# EL00117.net
KiCad netlist of a schematic drawn in EAGLE
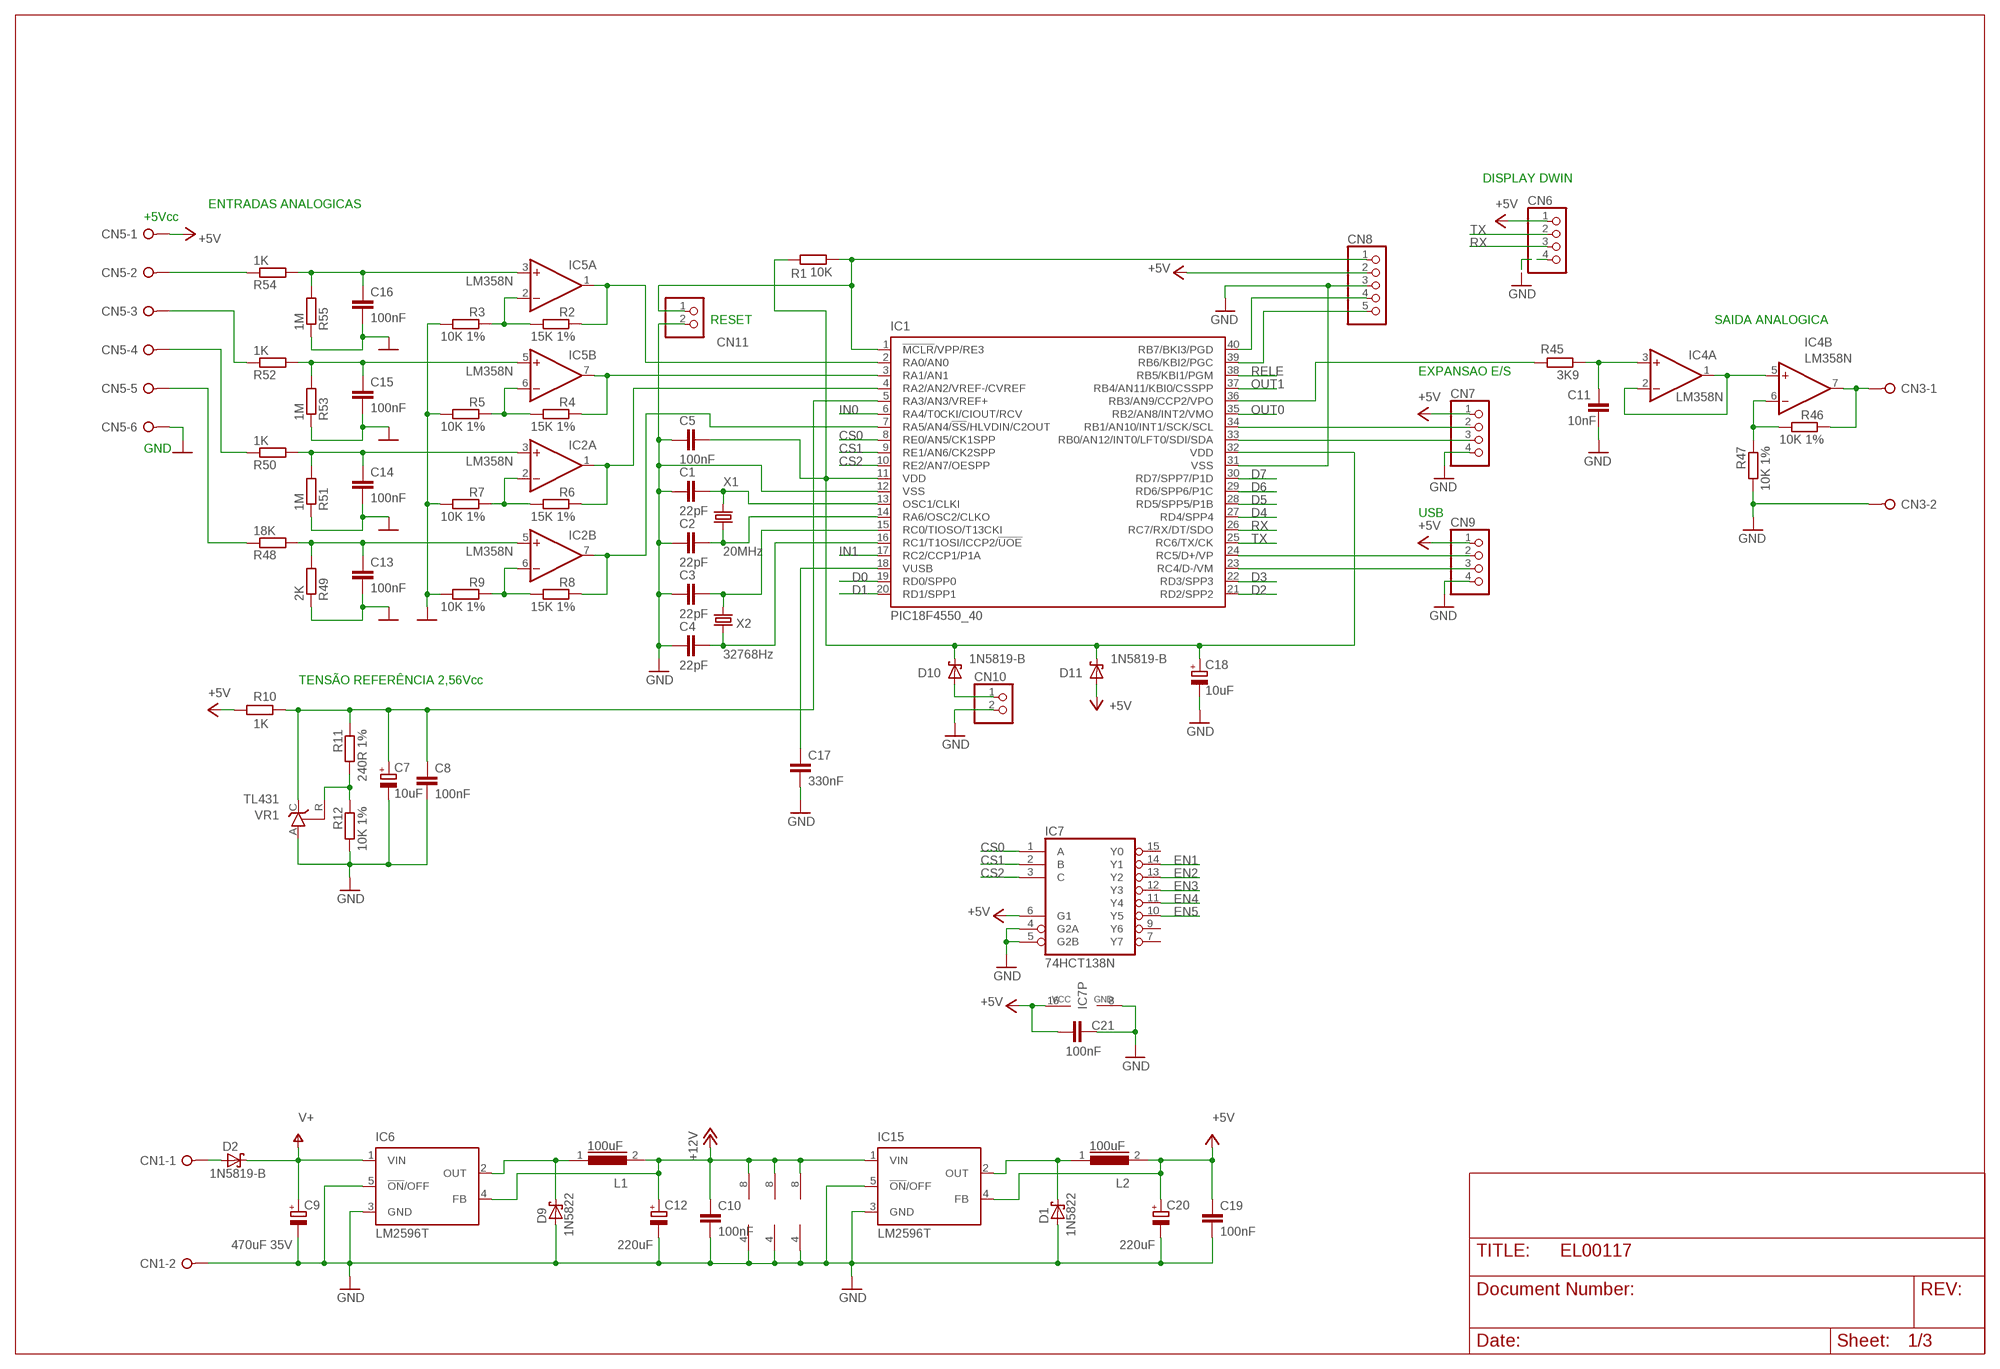
[diagram p0: schematic, sheet 1]
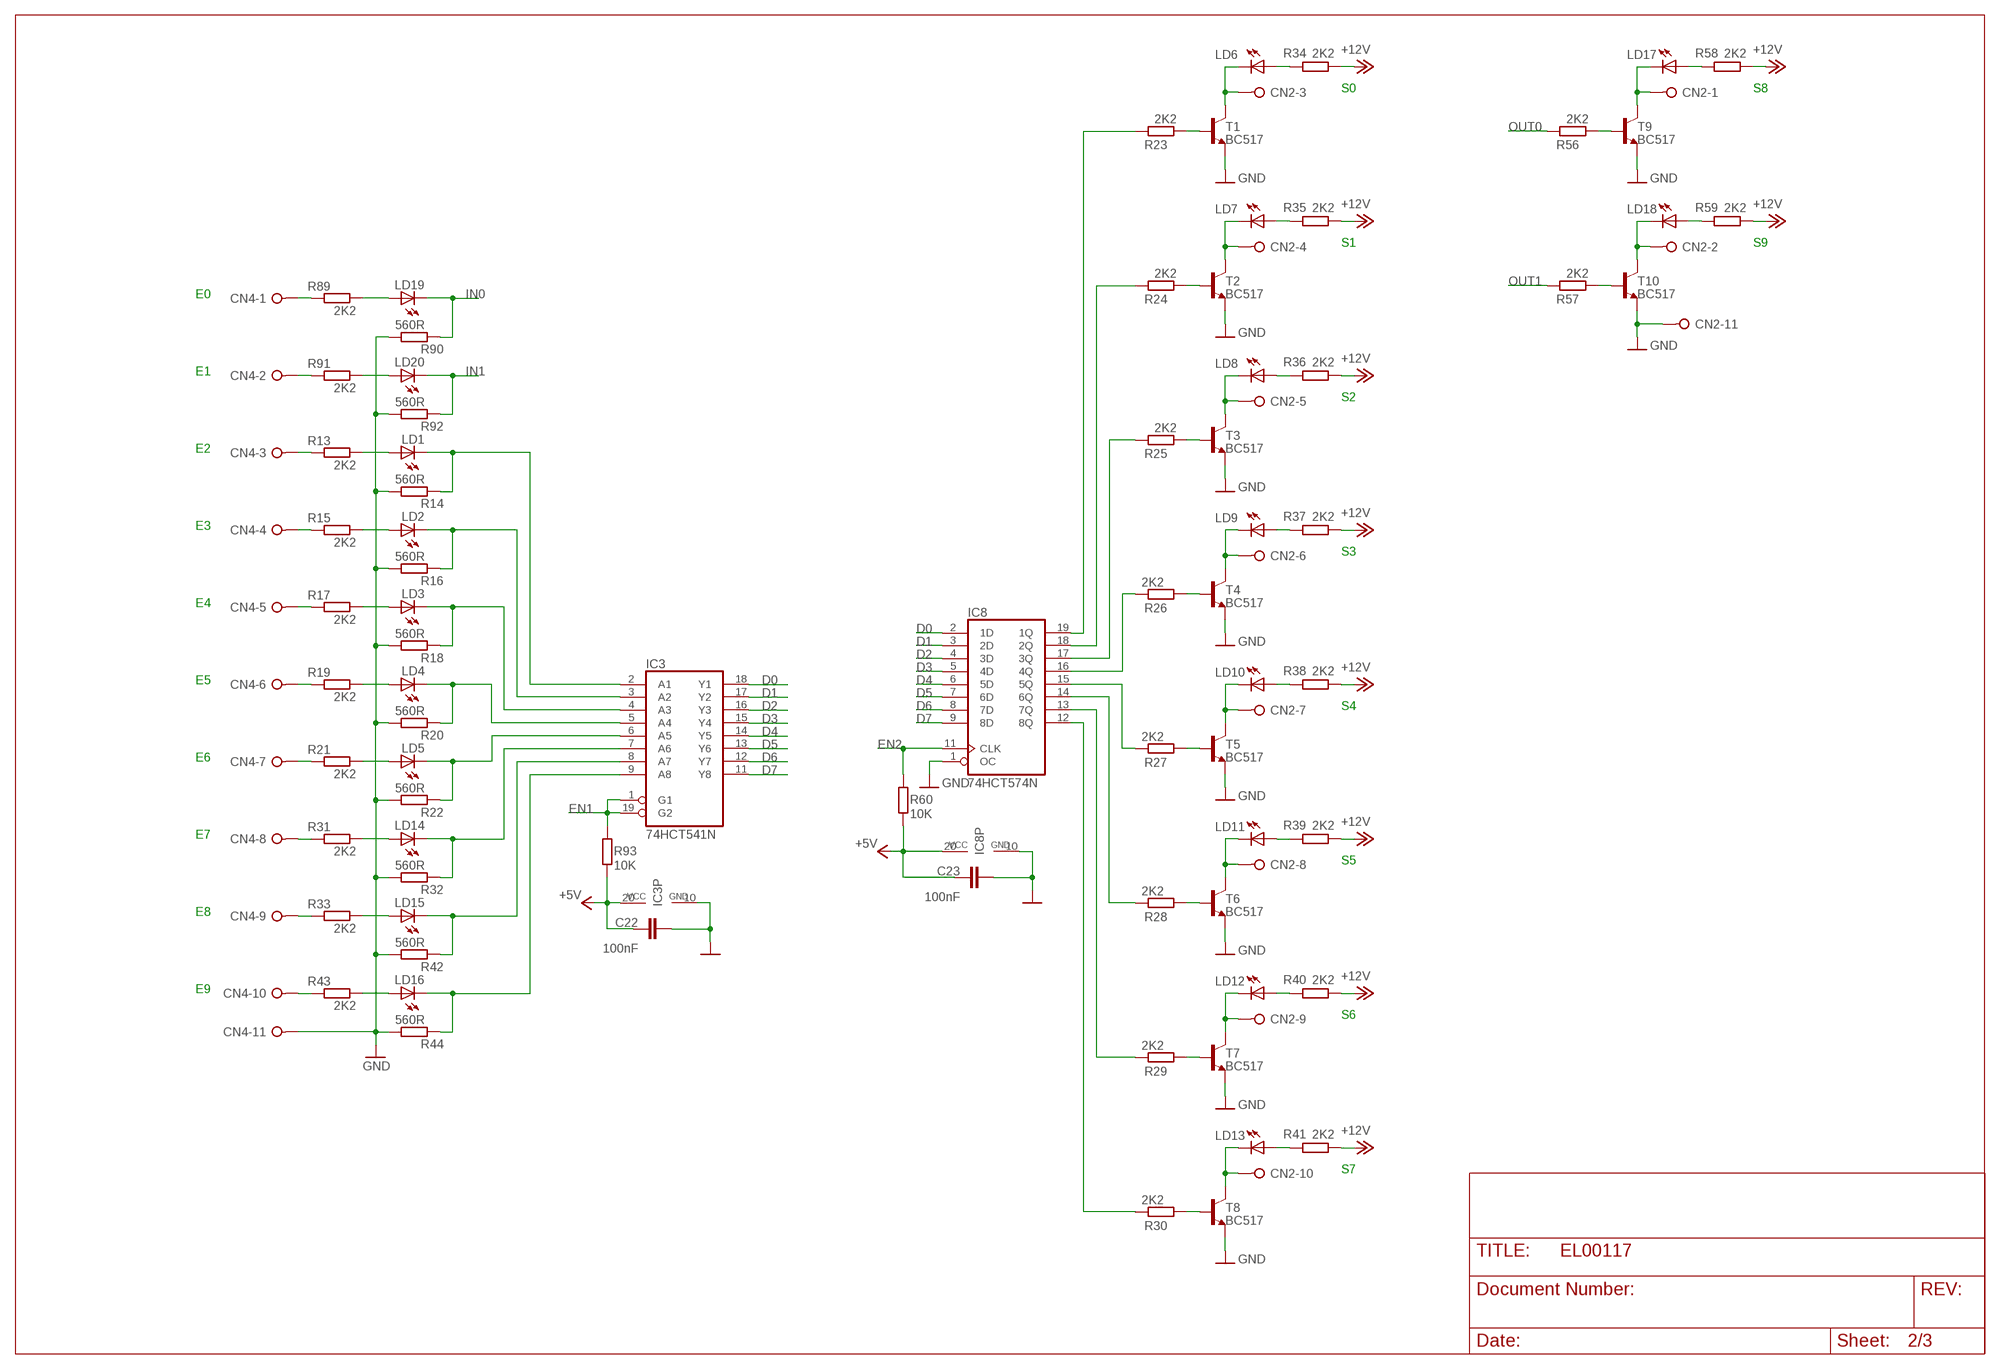
[diagram p1: schematic, sheet 2]
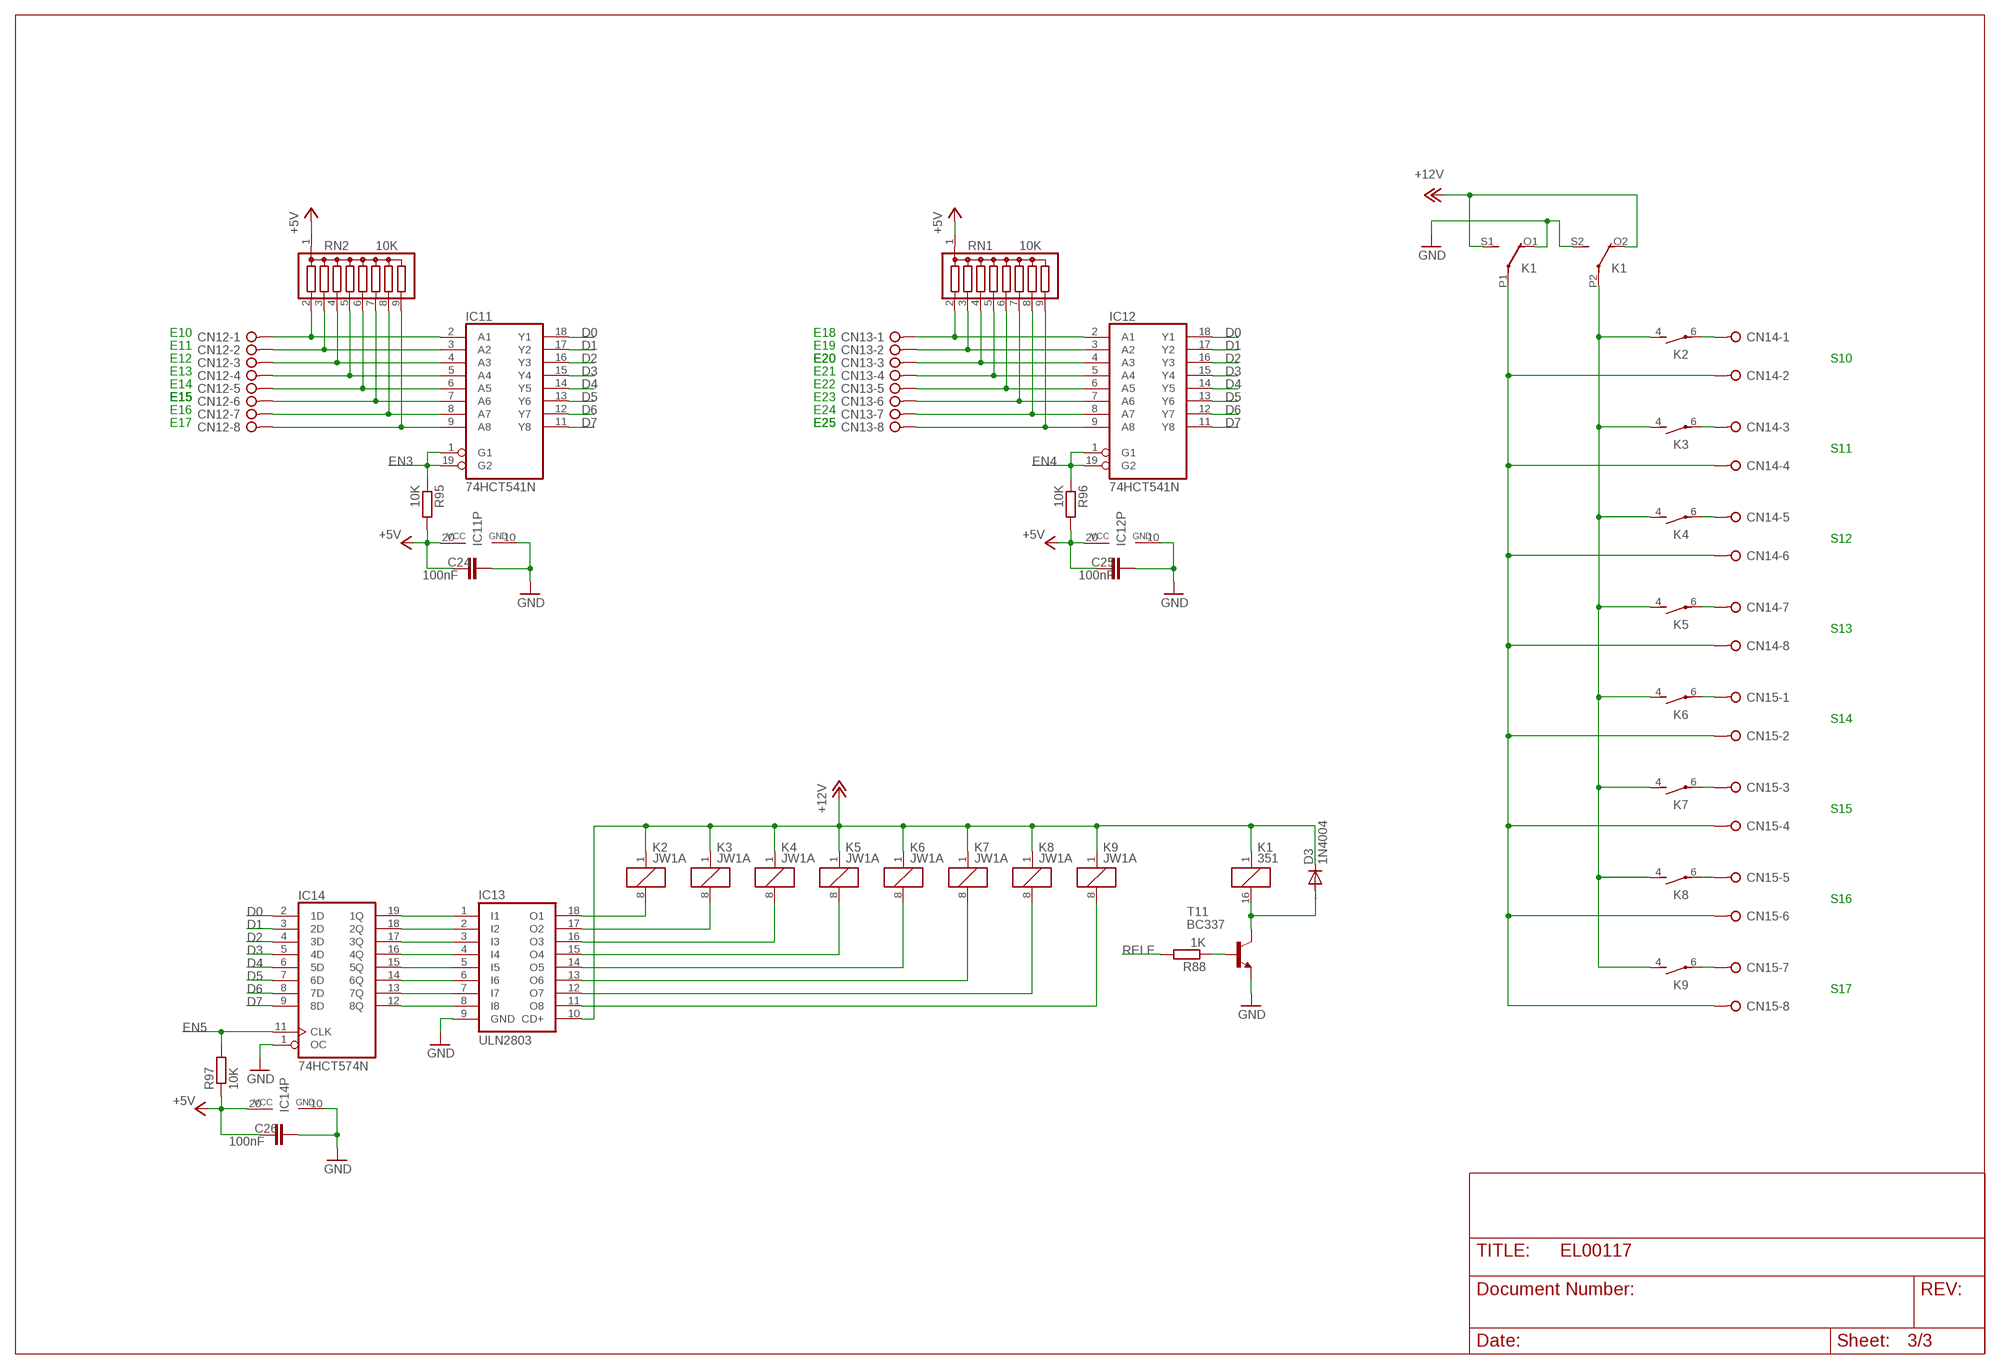
[diagram p2: schematic, sheet 3]

(export (version "E")
  (design (tool "Eeschema 10.0.6"))
  (components
    (comp (ref "C22")
      (value "100nF")
      (footprint "eagle-import:C050-024X044")
      (libsource (lib "eagle-import") (part "C-EU050-024X044"))
    )
    (comp (ref "C23")
      (value "100nF")
      (footprint "eagle-import:C050-024X044")
      (libsource (lib "eagle-import") (part "C-EU050-024X044"))
    )
    (comp (ref "CN2")
      (value "W237-11P")
      (footprint "eagle-import:W237-11P")
      (libsource (lib "eagle-import") (part "W237-11P"))
    )
    (comp (ref "CN4")
      (value "W237-11P")
      (footprint "eagle-import:W237-11P")
      (libsource (lib "eagle-import") (part "W237-11P"))
    )
    (comp (ref "IC3")
      (value "74HCT541N")
      (footprint "eagle-import:DIL20")
      (libsource (lib "eagle-import") (part "74541NHCT"))
    )
    (comp (ref "IC8")
      (value "74HCT574N")
      (footprint "eagle-import:DIL20")
      (libsource (lib "eagle-import") (part "74574NHCT"))
    )
    (comp (ref "LD1")
      (value "LED3MM")
      (footprint "eagle-import:LED3MM")
      (libsource (lib "eagle-import") (part "LED3MM"))
    )
    (comp (ref "LD2")
      (value "LED3MM")
      (footprint "eagle-import:LED3MM")
      (libsource (lib "eagle-import") (part "LED3MM"))
    )
    (comp (ref "LD3")
      (value "LED3MM")
      (footprint "eagle-import:LED3MM")
      (libsource (lib "eagle-import") (part "LED3MM"))
    )
    (comp (ref "LD4")
      (value "LED3MM")
      (footprint "eagle-import:LED3MM")
      (libsource (lib "eagle-import") (part "LED3MM"))
    )
    (comp (ref "LD5")
      (value "LED3MM")
      (footprint "eagle-import:LED3MM")
      (libsource (lib "eagle-import") (part "LED3MM"))
    )
    (comp (ref "LD6")
      (value "LED3MM")
      (footprint "eagle-import:LED3MM")
      (libsource (lib "eagle-import") (part "LED3MM"))
    )
    (comp (ref "LD7")
      (value "LED3MM")
      (footprint "eagle-import:LED3MM")
      (libsource (lib "eagle-import") (part "LED3MM"))
    )
    (comp (ref "LD8")
      (value "LED3MM")
      (footprint "eagle-import:LED3MM")
      (libsource (lib "eagle-import") (part "LED3MM"))
    )
    (comp (ref "LD9")
      (value "LED3MM")
      (footprint "eagle-import:LED3MM")
      (libsource (lib "eagle-import") (part "LED3MM"))
    )
    (comp (ref "LD10")
      (value "LED3MM")
      (footprint "eagle-import:LED3MM")
      (libsource (lib "eagle-import") (part "LED3MM"))
    )
    (comp (ref "LD11")
      (value "LED3MM")
      (footprint "eagle-import:LED3MM")
      (libsource (lib "eagle-import") (part "LED3MM"))
    )
    (comp (ref "LD12")
      (value "LED3MM")
      (footprint "eagle-import:LED3MM")
      (libsource (lib "eagle-import") (part "LED3MM"))
    )
    (comp (ref "LD13")
      (value "LED3MM")
      (footprint "eagle-import:LED3MM")
      (libsource (lib "eagle-import") (part "LED3MM"))
    )
    (comp (ref "LD14")
      (value "LED3MM")
      (footprint "eagle-import:LED3MM")
      (libsource (lib "eagle-import") (part "LED3MM"))
    )
    (comp (ref "LD15")
      (value "LED3MM")
      (footprint "eagle-import:LED3MM")
      (libsource (lib "eagle-import") (part "LED3MM"))
    )
    (comp (ref "LD16")
      (value "LED3MM")
      (footprint "eagle-import:LED3MM")
      (libsource (lib "eagle-import") (part "LED3MM"))
    )
    (comp (ref "LD17")
      (value "LED3MM")
      (footprint "eagle-import:LED3MM")
      (libsource (lib "eagle-import") (part "LED3MM"))
    )
    (comp (ref "LD18")
      (value "LED3MM")
      (footprint "eagle-import:LED3MM")
      (libsource (lib "eagle-import") (part "LED3MM"))
    )
    (comp (ref "LD19")
      (value "LED3MM")
      (footprint "eagle-import:LED3MM")
      (libsource (lib "eagle-import") (part "LED3MM"))
    )
    (comp (ref "LD20")
      (value "LED3MM")
      (footprint "eagle-import:LED3MM")
      (libsource (lib "eagle-import") (part "LED3MM"))
    )
    (comp (ref "R13")
      (value "2K2")
      (footprint "eagle-import:0309V")
      (libsource (lib "eagle-import") (part "R-EU_0309/V"))
    )
    (comp (ref "R14")
      (value "560R")
      (footprint "eagle-import:0309V")
      (libsource (lib "eagle-import") (part "R-EU_0309/V"))
    )
    (comp (ref "R15")
      (value "2K2")
      (footprint "eagle-import:0309V")
      (libsource (lib "eagle-import") (part "R-EU_0309/V"))
    )
    (comp (ref "R16")
      (value "560R")
      (footprint "eagle-import:0309V")
      (libsource (lib "eagle-import") (part "R-EU_0309/V"))
    )
    (comp (ref "R17")
      (value "2K2")
      (footprint "eagle-import:0309V")
      (libsource (lib "eagle-import") (part "R-EU_0309/V"))
    )
    (comp (ref "R18")
      (value "560R")
      (footprint "eagle-import:0309V")
      (libsource (lib "eagle-import") (part "R-EU_0309/V"))
    )
    (comp (ref "R19")
      (value "2K2")
      (footprint "eagle-import:0309V")
      (libsource (lib "eagle-import") (part "R-EU_0309/V"))
    )
    (comp (ref "R20")
      (value "560R")
      (footprint "eagle-import:0309V")
      (libsource (lib "eagle-import") (part "R-EU_0309/V"))
    )
    (comp (ref "R21")
      (value "2K2")
      (footprint "eagle-import:0309V")
      (libsource (lib "eagle-import") (part "R-EU_0309/V"))
    )
    (comp (ref "R22")
      (value "560R")
      (footprint "eagle-import:0309V")
      (libsource (lib "eagle-import") (part "R-EU_0309/V"))
    )
    (comp (ref "R23")
      (value "2K2")
      (footprint "eagle-import:0309V")
      (libsource (lib "eagle-import") (part "R-EU_0309/V"))
    )
    (comp (ref "R24")
      (value "2K2")
      (footprint "eagle-import:0309V")
      (libsource (lib "eagle-import") (part "R-EU_0309/V"))
    )
    (comp (ref "R25")
      (value "2K2")
      (footprint "eagle-import:0309V")
      (libsource (lib "eagle-import") (part "R-EU_0309/V"))
    )
    (comp (ref "R26")
      (value "2K2")
      (footprint "eagle-import:0309V")
      (libsource (lib "eagle-import") (part "R-EU_0309/V"))
    )
    (comp (ref "R27")
      (value "2K2")
      (footprint "eagle-import:0309V")
      (libsource (lib "eagle-import") (part "R-EU_0309/V"))
    )
    (comp (ref "R28")
      (value "2K2")
      (footprint "eagle-import:0309V")
      (libsource (lib "eagle-import") (part "R-EU_0309/V"))
    )
    (comp (ref "R29")
      (value "2K2")
      (footprint "eagle-import:0309V")
      (libsource (lib "eagle-import") (part "R-EU_0309/V"))
    )
    (comp (ref "R30")
      (value "2K2")
      (footprint "eagle-import:0309V")
      (libsource (lib "eagle-import") (part "R-EU_0309/V"))
    )
    (comp (ref "R31")
      (value "2K2")
      (footprint "eagle-import:0309V")
      (libsource (lib "eagle-import") (part "R-EU_0309/V"))
    )
    (comp (ref "R32")
      (value "560R")
      (footprint "eagle-import:0309V")
      (libsource (lib "eagle-import") (part "R-EU_0309/V"))
    )
    (comp (ref "R33")
      (value "2K2")
      (footprint "eagle-import:0309V")
      (libsource (lib "eagle-import") (part "R-EU_0309/V"))
    )
    (comp (ref "R34")
      (value "2K2")
      (footprint "eagle-import:0309V")
      (libsource (lib "eagle-import") (part "R-EU_0309/V"))
    )
    (comp (ref "R35")
      (value "2K2")
      (footprint "eagle-import:0309V")
      (libsource (lib "eagle-import") (part "R-EU_0309/V"))
    )
    (comp (ref "R36")
      (value "2K2")
      (footprint "eagle-import:0309V")
      (libsource (lib "eagle-import") (part "R-EU_0309/V"))
    )
    (comp (ref "R37")
      (value "2K2")
      (footprint "eagle-import:0309V")
      (libsource (lib "eagle-import") (part "R-EU_0309/V"))
    )
    (comp (ref "R38")
      (value "2K2")
      (footprint "eagle-import:0309V")
      (libsource (lib "eagle-import") (part "R-EU_0309/V"))
    )
    (comp (ref "R39")
      (value "2K2")
      (footprint "eagle-import:0309V")
      (libsource (lib "eagle-import") (part "R-EU_0309/V"))
    )
    (comp (ref "R40")
      (value "2K2")
      (footprint "eagle-import:0309V")
      (libsource (lib "eagle-import") (part "R-EU_0309/V"))
    )
    (comp (ref "R41")
      (value "2K2")
      (footprint "eagle-import:0309V")
      (libsource (lib "eagle-import") (part "R-EU_0309/V"))
    )
    (comp (ref "R42")
      (value "560R")
      (footprint "eagle-import:0309V")
      (libsource (lib "eagle-import") (part "R-EU_0309/V"))
    )
    (comp (ref "R43")
      (value "2K2")
      (footprint "eagle-import:0309V")
      (libsource (lib "eagle-import") (part "R-EU_0309/V"))
    )
    (comp (ref "R44")
      (value "560R")
      (footprint "eagle-import:0309V")
      (libsource (lib "eagle-import") (part "R-EU_0309/V"))
    )
    (comp (ref "R56")
      (value "2K2")
      (footprint "eagle-import:0309V")
      (libsource (lib "eagle-import") (part "R-EU_0309/V"))
    )
    (comp (ref "R57")
      (value "2K2")
      (footprint "eagle-import:0309V")
      (libsource (lib "eagle-import") (part "R-EU_0309/V"))
    )
    (comp (ref "R58")
      (value "2K2")
      (footprint "eagle-import:0309V")
      (libsource (lib "eagle-import") (part "R-EU_0309/V"))
    )
    (comp (ref "R59")
      (value "2K2")
      (footprint "eagle-import:0309V")
      (libsource (lib "eagle-import") (part "R-EU_0309/V"))
    )
    (comp (ref "R60")
      (value "10K")
      (footprint "eagle-import:0309V")
      (libsource (lib "eagle-import") (part "R-EU_0309/V"))
    )
    (comp (ref "R89")
      (value "2K2")
      (footprint "eagle-import:0309V")
      (libsource (lib "eagle-import") (part "R-EU_0309/V"))
    )
    (comp (ref "R90")
      (value "560R")
      (footprint "eagle-import:0309V")
      (libsource (lib "eagle-import") (part "R-EU_0309/V"))
    )
    (comp (ref "R91")
      (value "2K2")
      (footprint "eagle-import:0309V")
      (libsource (lib "eagle-import") (part "R-EU_0309/V"))
    )
    (comp (ref "R92")
      (value "560R")
      (footprint "eagle-import:0309V")
      (libsource (lib "eagle-import") (part "R-EU_0309/V"))
    )
    (comp (ref "R93")
      (value "10K")
      (footprint "eagle-import:0309V")
      (libsource (lib "eagle-import") (part "R-EU_0309/V"))
    )
    (comp (ref "T1")
      (value "BC517")
      (footprint "eagle-import:TO92-CBE")
      (libsource (lib "eagle-import") (part "-NPN-TO92-CBEBC517"))
    )
    (comp (ref "T2")
      (value "BC517")
      (footprint "eagle-import:TO92-CBE")
      (libsource (lib "eagle-import") (part "-NPN-TO92-CBEBC517"))
    )
    (comp (ref "T3")
      (value "BC517")
      (footprint "eagle-import:TO92-CBE")
      (libsource (lib "eagle-import") (part "-NPN-TO92-CBEBC517"))
    )
    (comp (ref "T4")
      (value "BC517")
      (footprint "eagle-import:TO92-CBE")
      (libsource (lib "eagle-import") (part "-NPN-TO92-CBEBC517"))
    )
    (comp (ref "T5")
      (value "BC517")
      (footprint "eagle-import:TO92-CBE")
      (libsource (lib "eagle-import") (part "-NPN-TO92-CBEBC517"))
    )
    (comp (ref "T6")
      (value "BC517")
      (footprint "eagle-import:TO92-CBE")
      (libsource (lib "eagle-import") (part "-NPN-TO92-CBEBC517"))
    )
    (comp (ref "T7")
      (value "BC517")
      (footprint "eagle-import:TO92-CBE")
      (libsource (lib "eagle-import") (part "-NPN-TO92-CBEBC517"))
    )
    (comp (ref "T8")
      (value "BC517")
      (footprint "eagle-import:TO92-CBE")
      (libsource (lib "eagle-import") (part "-NPN-TO92-CBEBC517"))
    )
    (comp (ref "T9")
      (value "BC517")
      (footprint "eagle-import:TO92-CBE")
      (libsource (lib "eagle-import") (part "-NPN-TO92-CBEBC517"))
    )
    (comp (ref "T10")
      (value "BC517")
      (footprint "eagle-import:TO92-CBE")
      (libsource (lib "eagle-import") (part "-NPN-TO92-CBEBC517"))
    )
    (comp (ref "C24")
      (value "100nF")
      (footprint "eagle-import:C050-024X044")
      (libsource (lib "eagle-import") (part "C-EU050-024X044"))
    )
    (comp (ref "C25")
      (value "100nF")
      (footprint "eagle-import:C050-024X044")
      (libsource (lib "eagle-import") (part "C-EU050-024X044"))
    )
    (comp (ref "C26")
      (value "100nF")
      (footprint "eagle-import:C050-024X044")
      (libsource (lib "eagle-import") (part "C-EU050-024X044"))
    )
    (comp (ref "CN12")
      (value "W237-08P")
      (footprint "eagle-import:W237-8P")
      (libsource (lib "eagle-import") (part "W237-08P"))
    )
    (comp (ref "CN13")
      (value "W237-08P")
      (footprint "eagle-import:W237-8P")
      (libsource (lib "eagle-import") (part "W237-08P"))
    )
    (comp (ref "CN14")
      (value "W237-08P")
      (footprint "eagle-import:W237-8P")
      (libsource (lib "eagle-import") (part "W237-08P"))
    )
    (comp (ref "CN15")
      (value "W237-08P")
      (footprint "eagle-import:W237-8P")
      (libsource (lib "eagle-import") (part "W237-08P"))
    )
    (comp (ref "D3")
      (value "1N4004")
      (footprint "eagle-import:DO41-10")
      (libsource (lib "eagle-import") (part "1N4004"))
    )
    (comp (ref "IC11")
      (value "74HCT541N")
      (footprint "eagle-import:DIL20")
      (libsource (lib "eagle-import") (part "74541NHCT"))
    )
    (comp (ref "IC12")
      (value "74HCT541N")
      (footprint "eagle-import:DIL20")
      (libsource (lib "eagle-import") (part "74541NHCT"))
    )
    (comp (ref "IC13")
      (value "ULN2803")
      (footprint "eagle-import:DIL18")
      (libsource (lib "eagle-import") (part "ULN2803A"))
    )
    (comp (ref "IC14")
      (value "74HCT574N")
      (footprint "eagle-import:DIL20")
      (libsource (lib "eagle-import") (part "74574NHCT"))
    )
    (comp (ref "K1")
      (value "351")
      (footprint "eagle-import:351")
      (libsource (lib "eagle-import") (part "351"))
    )
    (comp (ref "K2")
      (value "JW1A")
      (footprint "eagle-import:JW1A")
      (libsource (lib "eagle-import") (part "JW1A"))
    )
    (comp (ref "K3")
      (value "JW1A")
      (footprint "eagle-import:JW1A")
      (libsource (lib "eagle-import") (part "JW1A"))
    )
    (comp (ref "K4")
      (value "JW1A")
      (footprint "eagle-import:JW1A")
      (libsource (lib "eagle-import") (part "JW1A"))
    )
    (comp (ref "K5")
      (value "JW1A")
      (footprint "eagle-import:JW1A")
      (libsource (lib "eagle-import") (part "JW1A"))
    )
    (comp (ref "K6")
      (value "JW1A")
      (footprint "eagle-import:JW1A")
      (libsource (lib "eagle-import") (part "JW1A"))
    )
    (comp (ref "K7")
      (value "JW1A")
      (footprint "eagle-import:JW1A")
      (libsource (lib "eagle-import") (part "JW1A"))
    )
    (comp (ref "K8")
      (value "JW1A")
      (footprint "eagle-import:JW1A")
      (libsource (lib "eagle-import") (part "JW1A"))
    )
    (comp (ref "K9")
      (value "JW1A")
      (footprint "eagle-import:JW1A")
      (libsource (lib "eagle-import") (part "JW1A"))
    )
    (comp (ref "R88")
      (value "1K")
      (footprint "eagle-import:0309V")
      (libsource (lib "eagle-import") (part "R-EU_0309/V"))
    )
    (comp (ref "R95")
      (value "10K")
      (footprint "eagle-import:0309V")
      (libsource (lib "eagle-import") (part "R-EU_0309/V"))
    )
    (comp (ref "R96")
      (value "10K")
      (footprint "eagle-import:0309V")
      (libsource (lib "eagle-import") (part "R-EU_0309/V"))
    )
    (comp (ref "R97")
      (value "10K")
      (footprint "eagle-import:0309V")
      (libsource (lib "eagle-import") (part "R-EU_0309/V"))
    )
    (comp (ref "RN1")
      (value "10K")
      (footprint "eagle-import:SIL9")
      (libsource (lib "eagle-import") (part "G08R"))
    )
    (comp (ref "RN2")
      (value "10K")
      (footprint "eagle-import:SIL9")
      (libsource (lib "eagle-import") (part "G08R"))
    )
    (comp (ref "T11")
      (value "BC337")
      (footprint "eagle-import:TO92")
      (libsource (lib "eagle-import") (part "BC337"))
    )
    (comp (ref "C1")
      (value "22pF")
      (footprint "eagle-import:C050-024X044")
      (libsource (lib "eagle-import") (part "C-EU050-024X044"))
    )
    (comp (ref "C2")
      (value "22pF")
      (footprint "eagle-import:C050-024X044")
      (libsource (lib "eagle-import") (part "C-EU050-024X044"))
    )
    (comp (ref "C3")
      (value "22pF")
      (footprint "eagle-import:C050-024X044")
      (libsource (lib "eagle-import") (part "C-EU050-024X044"))
    )
    (comp (ref "C4")
      (value "22pF")
      (footprint "eagle-import:C050-024X044")
      (libsource (lib "eagle-import") (part "C-EU050-024X044"))
    )
    (comp (ref "C5")
      (value "100nF")
      (footprint "eagle-import:C050-024X044")
      (libsource (lib "eagle-import") (part "C-EU050-024X044"))
    )
    (comp (ref "C7")
      (value "10uF")
      (footprint "eagle-import:E2,5-6")
      (libsource (lib "eagle-import") (part "CPOL-EUE2.5-6"))
    )
    (comp (ref "C8")
      (value "100nF")
      (footprint "eagle-import:C050-024X044")
      (libsource (lib "eagle-import") (part "C-EU050-024X044"))
    )
    (comp (ref "C9")
      (value "470uF 35V")
      (footprint "eagle-import:E3,5-10")
      (libsource (lib "eagle-import") (part "CPOL-EUE3.5-10"))
    )
    (comp (ref "C10")
      (value "100nF")
      (footprint "eagle-import:C050-024X044")
      (libsource (lib "eagle-import") (part "C-EU050-024X044"))
    )
    (comp (ref "C11")
      (value "10nF")
      (footprint "eagle-import:C050-024X044")
      (libsource (lib "eagle-import") (part "C-EU050-024X044"))
    )
    (comp (ref "C12")
      (value "220uF")
      (footprint "eagle-import:E2,5-5")
      (libsource (lib "eagle-import") (part "CPOL-EUE2.5-5"))
    )
    (comp (ref "C13")
      (value "100nF")
      (footprint "eagle-import:C050-024X044")
      (libsource (lib "eagle-import") (part "C-EU050-024X044"))
    )
    (comp (ref "C14")
      (value "100nF")
      (footprint "eagle-import:C050-024X044")
      (libsource (lib "eagle-import") (part "C-EU050-024X044"))
    )
    (comp (ref "C15")
      (value "100nF")
      (footprint "eagle-import:C050-024X044")
      (libsource (lib "eagle-import") (part "C-EU050-024X044"))
    )
    (comp (ref "C16")
      (value "100nF")
      (footprint "eagle-import:C050-024X044")
      (libsource (lib "eagle-import") (part "C-EU050-024X044"))
    )
    (comp (ref "C17")
      (value "330nF")
      (footprint "eagle-import:C050-024X044")
      (libsource (lib "eagle-import") (part "C-EU050-024X044"))
    )
    (comp (ref "C18")
      (value "10uF")
      (footprint "eagle-import:E2,5-6")
      (libsource (lib "eagle-import") (part "CPOL-EUE2.5-6"))
    )
    (comp (ref "C19")
      (value "100nF")
      (footprint "eagle-import:C050-024X044")
      (libsource (lib "eagle-import") (part "C-EU050-024X044"))
    )
    (comp (ref "C20")
      (value "220uF")
      (footprint "eagle-import:E2,5-5")
      (libsource (lib "eagle-import") (part "CPOL-EUE2.5-5"))
    )
    (comp (ref "C21")
      (value "100nF")
      (footprint "eagle-import:C050-024X044")
      (libsource (lib "eagle-import") (part "C-EU050-024X044"))
    )
    (comp (ref "CN1")
      (value "W237-02P")
      (footprint "eagle-import:W237-132")
      (libsource (lib "eagle-import") (part "W237-02P"))
    )
    (comp (ref "CN3")
      (value "W237-02P")
      (footprint "eagle-import:W237-132")
      (libsource (lib "eagle-import") (part "W237-02P"))
    )
    (comp (ref "CN5")
      (value "W237-06P")
      (footprint "eagle-import:W237-6P")
      (libsource (lib "eagle-import") (part "W237-06P"))
    )
    (comp (ref "CN6")
      (value "PINHD-1X4")
      (footprint "eagle-import:1X04")
      (libsource (lib "eagle-import") (part "PINHD-1X4"))
    )
    (comp (ref "CN7")
      (value "PINHD-1X4")
      (footprint "eagle-import:1X04")
      (libsource (lib "eagle-import") (part "PINHD-1X4"))
    )
    (comp (ref "CN8")
      (value "PINHD-1X5")
      (footprint "eagle-import:1X05")
      (libsource (lib "eagle-import") (part "PINHD-1X5"))
    )
    (comp (ref "CN9")
      (value "PINHD-1X4")
      (footprint "eagle-import:1X04")
      (libsource (lib "eagle-import") (part "PINHD-1X4"))
    )
    (comp (ref "CN10")
      (value "PINHD-1X2")
      (footprint "eagle-import:1X02")
      (libsource (lib "eagle-import") (part "PINHD-1X2"))
    )
    (comp (ref "CN11")
      (value "PINHD-1X2")
      (footprint "eagle-import:1X02")
      (libsource (lib "eagle-import") (part "PINHD-1X2"))
    )
    (comp (ref "D1")
      (value "1N5822")
      (footprint "eagle-import:DO41-7.6")
      (libsource (lib "eagle-import") (part "1N5819-B"))
    )
    (comp (ref "D2")
      (value "1N5819-B")
      (footprint "eagle-import:DO41-7.6")
      (libsource (lib "eagle-import") (part "1N5819-B"))
    )
    (comp (ref "D9")
      (value "1N5822")
      (footprint "eagle-import:DO41-7.6")
      (libsource (lib "eagle-import") (part "1N5819-B"))
    )
    (comp (ref "D10")
      (value "1N5819-B")
      (footprint "eagle-import:DO41-7.6")
      (libsource (lib "eagle-import") (part "1N5819-B"))
    )
    (comp (ref "D11")
      (value "1N5819-B")
      (footprint "eagle-import:DO41-7.6")
      (libsource (lib "eagle-import") (part "1N5819-B"))
    )
    (comp (ref "IC1")
      (value "PIC18F4550_40")
      (footprint "eagle-import:DIL40")
      (fields (field (name "MF") "MICROCHIP") (field (name "MPN") "PIC18F4550-I/P"))
      (libsource (lib "eagle-import") (part "PIC18F4_40550"))
    )
    (comp (ref "IC2")
      (value "LM358N")
      (footprint "eagle-import:DIL08")
      (libsource (lib "eagle-import") (part "LM358N"))
    )
    (comp (ref "IC4")
      (value "LM358N")
      (footprint "eagle-import:DIL08")
      (libsource (lib "eagle-import") (part "LM358N"))
    )
    (comp (ref "IC5")
      (value "LM358N")
      (footprint "eagle-import:DIL08")
      (libsource (lib "eagle-import") (part "LM358N"))
    )
    (comp (ref "IC6")
      (value "LM2596T")
      (footprint "eagle-import:T05D")
      (fields (field (name "MPN") "LM2596T-ADJ/LF02"))
      (libsource (lib "eagle-import") (part "LM2596T"))
    )
    (comp (ref "IC7")
      (value "74HCT138N")
      (footprint "eagle-import:DIL16")
      (libsource (lib "eagle-import") (part "74138NHCT"))
    )
    (comp (ref "IC15")
      (value "LM2596T")
      (footprint "eagle-import:T05D")
      (fields (field (name "MPN") "LM2596T-ADJ/LF02"))
      (libsource (lib "eagle-import") (part "LM2596T"))
    )
    (comp (ref "L1")
      (value "100uF")
      (footprint "eagle-import:82114R")
      (libsource (lib "eagle-import") (part "82114R"))
    )
    (comp (ref "L2")
      (value "100uF")
      (footprint "eagle-import:82114R")
      (libsource (lib "eagle-import") (part "82114R"))
    )
    (comp (ref "R1")
      (value "10K")
      (footprint "eagle-import:0309V")
      (libsource (lib "eagle-import") (part "R-EU_0309/V"))
    )
    (comp (ref "R2")
      (value "15K 1%")
      (footprint "eagle-import:0309V")
      (libsource (lib "eagle-import") (part "R-EU_0309/V"))
    )
    (comp (ref "R3")
      (value "10K 1%")
      (footprint "eagle-import:0309V")
      (libsource (lib "eagle-import") (part "R-EU_0309/V"))
    )
    (comp (ref "R4")
      (value "15K 1%")
      (footprint "eagle-import:0309V")
      (libsource (lib "eagle-import") (part "R-EU_0309/V"))
    )
    (comp (ref "R5")
      (value "10K 1%")
      (footprint "eagle-import:0309V")
      (libsource (lib "eagle-import") (part "R-EU_0309/V"))
    )
    (comp (ref "R6")
      (value "15K 1%")
      (footprint "eagle-import:0309V")
      (libsource (lib "eagle-import") (part "R-EU_0309/V"))
    )
    (comp (ref "R7")
      (value "10K 1%")
      (footprint "eagle-import:0309V")
      (libsource (lib "eagle-import") (part "R-EU_0309/V"))
    )
    (comp (ref "R8")
      (value "15K 1%")
      (footprint "eagle-import:0309V")
      (libsource (lib "eagle-import") (part "R-EU_0309/V"))
    )
    (comp (ref "R9")
      (value "10K 1%")
      (footprint "eagle-import:0309V")
      (libsource (lib "eagle-import") (part "R-EU_0309/V"))
    )
    (comp (ref "R10")
      (value "1K")
      (footprint "eagle-import:0309V")
      (libsource (lib "eagle-import") (part "R-EU_0309/V"))
    )
    (comp (ref "R11")
      (value "240R 1%")
      (footprint "eagle-import:0309V")
      (libsource (lib "eagle-import") (part "R-EU_0309/V"))
    )
    (comp (ref "R12")
      (value "10K 1%")
      (footprint "eagle-import:0309V")
      (libsource (lib "eagle-import") (part "R-EU_0309/V"))
    )
    (comp (ref "R45")
      (value "3K9")
      (footprint "eagle-import:0309V")
      (libsource (lib "eagle-import") (part "R-EU_0309/V"))
    )
    (comp (ref "R46")
      (value "10K 1%")
      (footprint "eagle-import:0309V")
      (libsource (lib "eagle-import") (part "R-EU_0309/V"))
    )
    (comp (ref "R47")
      (value "10K 1%")
      (footprint "eagle-import:0309V")
      (libsource (lib "eagle-import") (part "R-EU_0309/V"))
    )
    (comp (ref "R48")
      (value "18K")
      (footprint "eagle-import:0309V")
      (libsource (lib "eagle-import") (part "R-EU_0309/V"))
    )
    (comp (ref "R49")
      (value "2K")
      (footprint "eagle-import:0309V")
      (libsource (lib "eagle-import") (part "R-EU_0309/V"))
    )
    (comp (ref "R50")
      (value "1K")
      (footprint "eagle-import:0309V")
      (libsource (lib "eagle-import") (part "R-EU_0309/V"))
    )
    (comp (ref "R51")
      (value "1M")
      (footprint "eagle-import:0309V")
      (libsource (lib "eagle-import") (part "R-EU_0309/V"))
    )
    (comp (ref "R52")
      (value "1K")
      (footprint "eagle-import:0309V")
      (libsource (lib "eagle-import") (part "R-EU_0309/V"))
    )
    (comp (ref "R53")
      (value "1M")
      (footprint "eagle-import:0309V")
      (libsource (lib "eagle-import") (part "R-EU_0309/V"))
    )
    (comp (ref "R54")
      (value "1K")
      (footprint "eagle-import:0309V")
      (libsource (lib "eagle-import") (part "R-EU_0309/V"))
    )
    (comp (ref "R55")
      (value "1M")
      (footprint "eagle-import:0309V")
      (libsource (lib "eagle-import") (part "R-EU_0309/V"))
    )
    (comp (ref "VR1")
      (value "TL431")
      (footprint "eagle-import:TO92-CLP")
      (libsource (lib "eagle-import") (part "TL431CLP"))
    )
    (comp (ref "X1")
      (value "20MHz")
      (footprint "eagle-import:HC49U-V")
      (libsource (lib "eagle-import") (part "CRYSTALHC49U-V"))
    )
    (comp (ref "X2")
      (value "32768Hz")
      (footprint "eagle-import:TC26V")
      (libsource (lib "eagle-import") (part "CRYSTALTC26V"))
    )
  )
  (nets
    (net (code "1") (name "+5V") (class "Default")
      (node (ref "C19") (pin "2") (pinfunction "2_2") (pintype "passive"))
      (node (ref "C20") (pin "+") (pinfunction "+_+") (pintype "passive"))
      (node (ref "C21") (pin "2") (pinfunction "2_2") (pintype "passive"))
      (node (ref "C22") (pin "1") (pinfunction "1_1") (pintype "passive"))
      (node (ref "C23") (pin "1") (pinfunction "1_1") (pintype "passive"))
      (node (ref "C24") (pin "1") (pinfunction "1_1") (pintype "passive"))
      (node (ref "C25") (pin "2") (pinfunction "2_2") (pintype "passive"))
      (node (ref "C26") (pin "2") (pinfunction "2_2") (pintype "passive"))
      (node (ref "CN5") (pin "1") (pinfunction "KL_1") (pintype "passive"))
      (node (ref "CN6") (pin "1") (pinfunction "1_1") (pintype "passive"))
      (node (ref "CN7") (pin "1") (pinfunction "1_1") (pintype "passive"))
      (node (ref "CN8") (pin "2") (pinfunction "2_2") (pintype "passive"))
      (node (ref "CN9") (pin "1") (pinfunction "1_1") (pintype "passive"))
      (node (ref "D11") (pin "A") (pinfunction "A_A") (pintype "passive"))
      (node (ref "IC11") (pin "20") (pinfunction "VCC_20") (pintype "power_in"))
      (node (ref "IC12") (pin "20") (pinfunction "VCC_20") (pintype "power_in"))
      (node (ref "IC14") (pin "20") (pinfunction "VCC_20") (pintype "power_in"))
      (node (ref "IC15") (pin "4") (pinfunction "FB_4") (pintype "input"))
      (node (ref "IC3") (pin "20") (pinfunction "VCC_20") (pintype "power_in"))
      (node (ref "IC7") (pin "16") (pinfunction "VCC_16") (pintype "power_in"))
      (node (ref "IC7") (pin "6") (pinfunction "G1_6") (pintype "input"))
      (node (ref "IC8") (pin "20") (pinfunction "VCC_20") (pintype "power_in"))
      (node (ref "L2") (pin "2") (pinfunction "2_2") (pintype "passive"))
      (node (ref "R10") (pin "2") (pinfunction "2_2") (pintype "passive"))
      (node (ref "R60") (pin "2") (pinfunction "2_2") (pintype "passive"))
      (node (ref "R93") (pin "2") (pinfunction "2_2") (pintype "passive"))
      (node (ref "R95") (pin "2") (pinfunction "2_2") (pintype "passive"))
      (node (ref "R96") (pin "2") (pinfunction "2_2") (pintype "passive"))
      (node (ref "R97") (pin "1") (pinfunction "1_1") (pintype "passive"))
      (node (ref "RN1") (pin "1") (pinfunction "1_1") (pintype "passive"))
      (node (ref "RN2") (pin "1") (pinfunction "1_1") (pintype "passive"))
    )
    (net (code "2") (name "+12V") (class "Default")
      (node (ref "C10") (pin "2") (pinfunction "2_2") (pintype "passive"))
      (node (ref "C12") (pin "+") (pinfunction "+_+") (pintype "passive"))
      (node (ref "D3") (pin "C") (pinfunction "C_C") (pintype "passive"))
      (node (ref "IC13") (pin "10") (pinfunction "CD+_10") (pintype "passive"))
      (node (ref "IC15") (pin "1") (pinfunction "VIN_1") (pintype "input"))
      (node (ref "IC2") (pin "8") (pinfunction "V+_8") (pintype "power_in"))
      (node (ref "IC4") (pin "8") (pinfunction "V+_8") (pintype "power_in"))
      (node (ref "IC5") (pin "8") (pinfunction "V+_8") (pintype "power_in"))
      (node (ref "IC6") (pin "4") (pinfunction "FB_4") (pintype "input"))
      (node (ref "K1") (pin "1") (pinfunction "1_1") (pintype "passive"))
      (node (ref "K1") (pin "O2") (pinfunction "O_O2") (pintype "passive"))
      (node (ref "K1") (pin "S1") (pinfunction "S_S1") (pintype "passive"))
      (node (ref "K2") (pin "1") (pinfunction "1_1") (pintype "passive"))
      (node (ref "K3") (pin "1") (pinfunction "1_1") (pintype "passive"))
      (node (ref "K4") (pin "1") (pinfunction "1_1") (pintype "passive"))
      (node (ref "K5") (pin "1") (pinfunction "1_1") (pintype "passive"))
      (node (ref "K6") (pin "1") (pinfunction "1_1") (pintype "passive"))
      (node (ref "K7") (pin "1") (pinfunction "1_1") (pintype "passive"))
      (node (ref "K8") (pin "1") (pinfunction "1_1") (pintype "passive"))
      (node (ref "K9") (pin "1") (pinfunction "1_1") (pintype "passive"))
      (node (ref "L1") (pin "2") (pinfunction "2_2") (pintype "passive"))
      (node (ref "R34") (pin "1") (pinfunction "1_1") (pintype "passive"))
      (node (ref "R35") (pin "1") (pinfunction "1_1") (pintype "passive"))
      (node (ref "R36") (pin "1") (pinfunction "1_1") (pintype "passive"))
      (node (ref "R37") (pin "1") (pinfunction "1_1") (pintype "passive"))
      (node (ref "R38") (pin "1") (pinfunction "1_1") (pintype "passive"))
      (node (ref "R39") (pin "1") (pinfunction "1_1") (pintype "passive"))
      (node (ref "R40") (pin "1") (pinfunction "1_1") (pintype "passive"))
      (node (ref "R41") (pin "1") (pinfunction "1_1") (pintype "passive"))
      (node (ref "R58") (pin "1") (pinfunction "1_1") (pintype "passive"))
      (node (ref "R59") (pin "1") (pinfunction "1_1") (pintype "passive"))
    )
    (net (code "3") (name "CS0") (class "Default")
      (node (ref "IC1") (pin "8") (pinfunction "RE0/AN5/CK1SPP_8") (pintype "bidirectional"))
      (node (ref "IC7") (pin "1") (pinfunction "A_1") (pintype "input"))
    )
    (net (code "4") (name "CS1") (class "Default")
      (node (ref "IC1") (pin "9") (pinfunction "RE1/AN6/CK2SPP_9") (pintype "bidirectional"))
      (node (ref "IC7") (pin "2") (pinfunction "B_2") (pintype "input"))
    )
    (net (code "5") (name "CS2") (class "Default")
      (node (ref "IC1") (pin "10") (pinfunction "RE2/AN7/OESPP_10") (pintype "bidirectional"))
      (node (ref "IC7") (pin "3") (pinfunction "C_3") (pintype "input"))
    )
    (net (code "6") (name "D0") (class "Default")
      (node (ref "IC1") (pin "19") (pinfunction "RD0/SPP0_19") (pintype "bidirectional"))
      (node (ref "IC11") (pin "18") (pinfunction "Y1_18") (pintype "tri_state"))
      (node (ref "IC12") (pin "18") (pinfunction "Y1_18") (pintype "tri_state"))
      (node (ref "IC14") (pin "2") (pinfunction "1D_2") (pintype "input"))
      (node (ref "IC3") (pin "18") (pinfunction "Y1_18") (pintype "tri_state"))
      (node (ref "IC8") (pin "2") (pinfunction "1D_2") (pintype "input"))
    )
    (net (code "7") (name "D1") (class "Default")
      (node (ref "IC1") (pin "20") (pinfunction "RD1/SPP1_20") (pintype "bidirectional"))
      (node (ref "IC11") (pin "17") (pinfunction "Y2_17") (pintype "tri_state"))
      (node (ref "IC12") (pin "17") (pinfunction "Y2_17") (pintype "tri_state"))
      (node (ref "IC14") (pin "3") (pinfunction "2D_3") (pintype "input"))
      (node (ref "IC3") (pin "17") (pinfunction "Y2_17") (pintype "tri_state"))
      (node (ref "IC8") (pin "3") (pinfunction "2D_3") (pintype "input"))
    )
    (net (code "8") (name "D2") (class "Default")
      (node (ref "IC1") (pin "21") (pinfunction "RD2/SPP2_21") (pintype "bidirectional"))
      (node (ref "IC11") (pin "16") (pinfunction "Y3_16") (pintype "tri_state"))
      (node (ref "IC12") (pin "16") (pinfunction "Y3_16") (pintype "tri_state"))
      (node (ref "IC14") (pin "4") (pinfunction "3D_4") (pintype "input"))
      (node (ref "IC3") (pin "16") (pinfunction "Y3_16") (pintype "tri_state"))
      (node (ref "IC8") (pin "4") (pinfunction "3D_4") (pintype "input"))
    )
    (net (code "9") (name "D3") (class "Default")
      (node (ref "IC1") (pin "22") (pinfunction "RD3/SPP3_22") (pintype "bidirectional"))
      (node (ref "IC11") (pin "15") (pinfunction "Y4_15") (pintype "tri_state"))
      (node (ref "IC12") (pin "15") (pinfunction "Y4_15") (pintype "tri_state"))
      (node (ref "IC14") (pin "5") (pinfunction "4D_5") (pintype "input"))
      (node (ref "IC3") (pin "15") (pinfunction "Y4_15") (pintype "tri_state"))
      (node (ref "IC8") (pin "5") (pinfunction "4D_5") (pintype "input"))
    )
    (net (code "10") (name "D4") (class "Default")
      (node (ref "IC1") (pin "27") (pinfunction "RD4/SPP4_27") (pintype "bidirectional"))
      (node (ref "IC11") (pin "14") (pinfunction "Y5_14") (pintype "tri_state"))
      (node (ref "IC12") (pin "14") (pinfunction "Y5_14") (pintype "tri_state"))
      (node (ref "IC14") (pin "6") (pinfunction "5D_6") (pintype "input"))
      (node (ref "IC3") (pin "14") (pinfunction "Y5_14") (pintype "tri_state"))
      (node (ref "IC8") (pin "6") (pinfunction "5D_6") (pintype "input"))
    )
    (net (code "11") (name "D5") (class "Default")
      (node (ref "IC1") (pin "28") (pinfunction "RD5/SPP5/P1B_28") (pintype "bidirectional"))
      (node (ref "IC11") (pin "13") (pinfunction "Y6_13") (pintype "tri_state"))
      (node (ref "IC12") (pin "13") (pinfunction "Y6_13") (pintype "tri_state"))
      (node (ref "IC14") (pin "7") (pinfunction "6D_7") (pintype "input"))
      (node (ref "IC3") (pin "13") (pinfunction "Y6_13") (pintype "tri_state"))
      (node (ref "IC8") (pin "7") (pinfunction "6D_7") (pintype "input"))
    )
    (net (code "12") (name "D6") (class "Default")
      (node (ref "IC1") (pin "29") (pinfunction "RD6/SPP6/P1C_29") (pintype "bidirectional"))
      (node (ref "IC11") (pin "12") (pinfunction "Y7_12") (pintype "tri_state"))
      (node (ref "IC12") (pin "12") (pinfunction "Y7_12") (pintype "tri_state"))
      (node (ref "IC14") (pin "8") (pinfunction "7D_8") (pintype "input"))
      (node (ref "IC3") (pin "12") (pinfunction "Y7_12") (pintype "tri_state"))
      (node (ref "IC8") (pin "8") (pinfunction "7D_8") (pintype "input"))
    )
    (net (code "13") (name "D7") (class "Default")
      (node (ref "IC1") (pin "30") (pinfunction "RD7/SPP7/P1D_30") (pintype "bidirectional"))
      (node (ref "IC11") (pin "11") (pinfunction "Y8_11") (pintype "tri_state"))
      (node (ref "IC12") (pin "11") (pinfunction "Y8_11") (pintype "tri_state"))
      (node (ref "IC14") (pin "9") (pinfunction "8D_9") (pintype "input"))
      (node (ref "IC3") (pin "11") (pinfunction "Y8_11") (pintype "tri_state"))
      (node (ref "IC8") (pin "9") (pinfunction "8D_9") (pintype "input"))
    )
    (net (code "14") (name "EN1") (class "Default")
      (node (ref "IC3") (pin "1") (pinfunction "G1_1") (pintype "input"))
      (node (ref "IC3") (pin "19") (pinfunction "G2_19") (pintype "input"))
      (node (ref "IC7") (pin "14") (pinfunction "Y1_14") (pintype "output"))
      (node (ref "R93") (pin "1") (pinfunction "1_1") (pintype "passive"))
    )
    (net (code "15") (name "EN2") (class "Default")
      (node (ref "IC7") (pin "13") (pinfunction "Y2_13") (pintype "output"))
      (node (ref "IC8") (pin "11") (pinfunction "CLK_11") (pintype "input"))
      (node (ref "R60") (pin "1") (pinfunction "1_1") (pintype "passive"))
    )
    (net (code "16") (name "EN3") (class "Default")
      (node (ref "IC11") (pin "1") (pinfunction "G1_1") (pintype "input"))
      (node (ref "IC11") (pin "19") (pinfunction "G2_19") (pintype "input"))
      (node (ref "IC7") (pin "12") (pinfunction "Y3_12") (pintype "output"))
      (node (ref "R95") (pin "1") (pinfunction "1_1") (pintype "passive"))
    )
    (net (code "17") (name "EN4") (class "Default")
      (node (ref "IC12") (pin "1") (pinfunction "G1_1") (pintype "input"))
      (node (ref "IC12") (pin "19") (pinfunction "G2_19") (pintype "input"))
      (node (ref "IC7") (pin "11") (pinfunction "Y4_11") (pintype "output"))
      (node (ref "R96") (pin "1") (pinfunction "1_1") (pintype "passive"))
    )
    (net (code "18") (name "EN5") (class "Default")
      (node (ref "IC14") (pin "11") (pinfunction "CLK_11") (pintype "input"))
      (node (ref "IC7") (pin "10") (pinfunction "Y5_10") (pintype "output"))
      (node (ref "R97") (pin "2") (pinfunction "2_2") (pintype "passive"))
    )
    (net (code "19") (name "GND") (class "Default")
      (node (ref "C1") (pin "1") (pinfunction "1_1") (pintype "passive"))
      (node (ref "C10") (pin "1") (pinfunction "1_1") (pintype "passive"))
      (node (ref "C11") (pin "1") (pinfunction "1_1") (pintype "passive"))
      (node (ref "C12") (pin "-") (pinfunction "-_-") (pintype "passive"))
      (node (ref "C13") (pin "1") (pinfunction "1_1") (pintype "passive"))
      (node (ref "C14") (pin "1") (pinfunction "1_1") (pintype "passive"))
      (node (ref "C15") (pin "1") (pinfunction "1_1") (pintype "passive"))
      (node (ref "C16") (pin "1") (pinfunction "1_1") (pintype "passive"))
      (node (ref "C17") (pin "1") (pinfunction "1_1") (pintype "passive"))
      (node (ref "C18") (pin "-") (pinfunction "-_-") (pintype "passive"))
      (node (ref "C19") (pin "1") (pinfunction "1_1") (pintype "passive"))
      (node (ref "C2") (pin "1") (pinfunction "1_1") (pintype "passive"))
      (node (ref "C20") (pin "-") (pinfunction "-_-") (pintype "passive"))
      (node (ref "C21") (pin "1") (pinfunction "1_1") (pintype "passive"))
      (node (ref "C22") (pin "2") (pinfunction "2_2") (pintype "passive"))
      (node (ref "C23") (pin "2") (pinfunction "2_2") (pintype "passive"))
      (node (ref "C24") (pin "2") (pinfunction "2_2") (pintype "passive"))
      (node (ref "C25") (pin "1") (pinfunction "1_1") (pintype "passive"))
      (node (ref "C26") (pin "1") (pinfunction "1_1") (pintype "passive"))
      (node (ref "C3") (pin "1") (pinfunction "1_1") (pintype "passive"))
      (node (ref "C4") (pin "1") (pinfunction "1_1") (pintype "passive"))
      (node (ref "C5") (pin "1") (pinfunction "1_1") (pintype "passive"))
      (node (ref "C7") (pin "-") (pinfunction "-_-") (pintype "passive"))
      (node (ref "C8") (pin "1") (pinfunction "1_1") (pintype "passive"))
      (node (ref "C9") (pin "-") (pinfunction "-_-") (pintype "passive"))
      (node (ref "CN1") (pin "2") (pinfunction "KL_2") (pintype "passive"))
      (node (ref "CN10") (pin "2") (pinfunction "2_2") (pintype "passive"))
      (node (ref "CN11") (pin "2") (pinfunction "2_2") (pintype "passive"))
      (node (ref "CN2") (pin "11") (pinfunction "KL_11") (pintype "passive"))
      (node (ref "CN3") (pin "2") (pinfunction "KL_2") (pintype "passive"))
      (node (ref "CN4") (pin "11") (pinfunction "KL_11") (pintype "passive"))
      (node (ref "CN5") (pin "6") (pinfunction "KL_6") (pintype "passive"))
      (node (ref "CN6") (pin "4") (pinfunction "4_4") (pintype "passive"))
      (node (ref "CN7") (pin "4") (pinfunction "4_4") (pintype "passive"))
      (node (ref "CN8") (pin "3") (pinfunction "3_3") (pintype "passive"))
      (node (ref "CN9") (pin "4") (pinfunction "4_4") (pintype "passive"))
      (node (ref "D1") (pin "A") (pinfunction "A_A") (pintype "passive"))
      (node (ref "D9") (pin "A") (pinfunction "A_A") (pintype "passive"))
      (node (ref "IC1") (pin "12") (pinfunction "VSS_12") (pintype "power_in"))
      (node (ref "IC1") (pin "31") (pinfunction "VSS_31") (pintype "power_in"))
      (node (ref "IC11") (pin "10") (pinfunction "GND_10") (pintype "power_in"))
      (node (ref "IC12") (pin "10") (pinfunction "GND_10") (pintype "power_in"))
      (node (ref "IC13") (pin "9") (pinfunction "GND_9") (pintype "power_in"))
      (node (ref "IC14") (pin "1") (pinfunction "OC_1") (pintype "input"))
      (node (ref "IC14") (pin "10") (pinfunction "GND_10") (pintype "power_in"))
      (node (ref "IC15") (pin "3") (pinfunction "GND_3") (pintype "power_in"))
      (node (ref "IC15") (pin "5") (pinfunction "~{ON}/OFF_5") (pintype "input"))
      (node (ref "IC2") (pin "4") (pinfunction "V-_4") (pintype "power_in"))
      (node (ref "IC3") (pin "10") (pinfunction "GND_10") (pintype "power_in"))
      (node (ref "IC4") (pin "4") (pinfunction "V-_4") (pintype "power_in"))
      (node (ref "IC5") (pin "4") (pinfunction "V-_4") (pintype "power_in"))
      (node (ref "IC6") (pin "3") (pinfunction "GND_3") (pintype "power_in"))
      (node (ref "IC6") (pin "5") (pinfunction "~{ON}/OFF_5") (pintype "input"))
      (node (ref "IC7") (pin "4") (pinfunction "G2A_4") (pintype "input"))
      (node (ref "IC7") (pin "5") (pinfunction "G2B_5") (pintype "input"))
      (node (ref "IC7") (pin "8") (pinfunction "GND_8") (pintype "power_in"))
      (node (ref "IC8") (pin "1") (pinfunction "OC_1") (pintype "input"))
      (node (ref "IC8") (pin "10") (pinfunction "GND_10") (pintype "power_in"))
      (node (ref "K1") (pin "O1") (pinfunction "O_O1") (pintype "passive"))
      (node (ref "K1") (pin "S2") (pinfunction "S_S2") (pintype "passive"))
      (node (ref "R12") (pin "2") (pinfunction "2_2") (pintype "passive"))
      (node (ref "R14") (pin "1") (pinfunction "1_1") (pintype "passive"))
      (node (ref "R16") (pin "1") (pinfunction "1_1") (pintype "passive"))
      (node (ref "R18") (pin "1") (pinfunction "1_1") (pintype "passive"))
      (node (ref "R20") (pin "1") (pinfunction "1_1") (pintype "passive"))
      (node (ref "R22") (pin "1") (pinfunction "1_1") (pintype "passive"))
      (node (ref "R3") (pin "2") (pinfunction "2_2") (pintype "passive"))
      (node (ref "R32") (pin "1") (pinfunction "1_1") (pintype "passive"))
      (node (ref "R42") (pin "1") (pinfunction "1_1") (pintype "passive"))
      (node (ref "R44") (pin "1") (pinfunction "1_1") (pintype "passive"))
      (node (ref "R47") (pin "2") (pinfunction "2_2") (pintype "passive"))
      (node (ref "R49") (pin "1") (pinfunction "1_1") (pintype "passive"))
      (node (ref "R5") (pin "2") (pinfunction "2_2") (pintype "passive"))
      (node (ref "R51") (pin "1") (pinfunction "1_1") (pintype "passive"))
      (node (ref "R53") (pin "1") (pinfunction "1_1") (pintype "passive"))
      (node (ref "R55") (pin "1") (pinfunction "1_1") (pintype "passive"))
      (node (ref "R7") (pin "2") (pinfunction "2_2") (pintype "passive"))
      (node (ref "R9") (pin "2") (pinfunction "2_2") (pintype "passive"))
      (node (ref "R90") (pin "1") (pinfunction "1_1") (pintype "passive"))
      (node (ref "R92") (pin "1") (pinfunction "1_1") (pintype "passive"))
      (node (ref "T1") (pin "E") (pinfunction "E_E") (pintype "passive"))
      (node (ref "T10") (pin "E") (pinfunction "E_E") (pintype "passive"))
      (node (ref "T11") (pin "1") (pinfunction "E_1") (pintype "passive"))
      (node (ref "T2") (pin "E") (pinfunction "E_E") (pintype "passive"))
      (node (ref "T3") (pin "E") (pinfunction "E_E") (pintype "passive"))
      (node (ref "T4") (pin "E") (pinfunction "E_E") (pintype "passive"))
      (node (ref "T5") (pin "E") (pinfunction "E_E") (pintype "passive"))
      (node (ref "T6") (pin "E") (pinfunction "E_E") (pintype "passive"))
      (node (ref "T7") (pin "E") (pinfunction "E_E") (pintype "passive"))
      (node (ref "T8") (pin "E") (pinfunction "E_E") (pintype "passive"))
      (node (ref "T9") (pin "E") (pinfunction "E_E") (pintype "passive"))
      (node (ref "VR1") (pin "A") (pinfunction "A_A") (pintype "passive"))
    )
    (net (code "20") (name "IN0") (class "Default")
      (node (ref "IC1") (pin "6") (pinfunction "RA4/T0CKI/CIOUT/RCV_6") (pintype "bidirectional"))
      (node (ref "LD19") (pin "K") (pinfunction "C_K") (pintype "passive"))
      (node (ref "R90") (pin "2") (pinfunction "2_2") (pintype "passive"))
    )
    (net (code "21") (name "IN1") (class "Default")
      (node (ref "IC1") (pin "17") (pinfunction "RC2/CCP1/P1A_17") (pintype "bidirectional"))
      (node (ref "LD20") (pin "K") (pinfunction "C_K") (pintype "passive"))
      (node (ref "R92") (pin "2") (pinfunction "2_2") (pintype "passive"))
    )
    (net (code "22") (name "Net-(C18-Pad+)") (class "Default")
      (node (ref "C18") (pin "+") (pinfunction "+_+") (pintype "passive"))
      (node (ref "C5") (pin "2") (pinfunction "2_2") (pintype "passive"))
      (node (ref "D10") (pin "C") (pinfunction "C_C") (pintype "passive"))
      (node (ref "D11") (pin "C") (pinfunction "C_C") (pintype "passive"))
      (node (ref "IC1") (pin "11") (pinfunction "VDD_11") (pintype "power_in"))
      (node (ref "IC1") (pin "32") (pinfunction "VDD_32") (pintype "power_in"))
      (node (ref "R1") (pin "2") (pinfunction "2_2") (pintype "passive"))
    )
    (net (code "23") (name "Net-(CN1A-KL)") (class "Default")
      (node (ref "CN1") (pin "1") (pinfunction "KL_1") (pintype "passive"))
      (node (ref "D2") (pin "A") (pinfunction "A_A") (pintype "passive"))
    )
    (net (code "24") (name "Net-(CN2A-KL)") (class "Default")
      (node (ref "CN2") (pin "1") (pinfunction "KL_1") (pintype "passive"))
      (node (ref "LD17") (pin "K") (pinfunction "C_K") (pintype "passive"))
      (node (ref "T9") (pin "C") (pinfunction "C_C") (pintype "passive"))
    )
    (net (code "25") (name "Net-(CN2B-KL)") (class "Default")
      (node (ref "CN2") (pin "10") (pinfunction "KL_10") (pintype "passive"))
      (node (ref "LD13") (pin "K") (pinfunction "C_K") (pintype "passive"))
      (node (ref "T8") (pin "C") (pinfunction "C_C") (pintype "passive"))
    )
    (net (code "26") (name "Net-(CN2D-KL)") (class "Default")
      (node (ref "CN2") (pin "2") (pinfunction "KL_2") (pintype "passive"))
      (node (ref "LD18") (pin "K") (pinfunction "C_K") (pintype "passive"))
      (node (ref "T10") (pin "C") (pinfunction "C_C") (pintype "passive"))
    )
    (net (code "27") (name "Net-(CN2E-KL)") (class "Default")
      (node (ref "CN2") (pin "3") (pinfunction "KL_3") (pintype "passive"))
      (node (ref "LD6") (pin "K") (pinfunction "C_K") (pintype "passive"))
      (node (ref "T1") (pin "C") (pinfunction "C_C") (pintype "passive"))
    )
    (net (code "28") (name "Net-(CN2F-KL)") (class "Default")
      (node (ref "CN2") (pin "4") (pinfunction "KL_4") (pintype "passive"))
      (node (ref "LD7") (pin "K") (pinfunction "C_K") (pintype "passive"))
      (node (ref "T2") (pin "C") (pinfunction "C_C") (pintype "passive"))
    )
    (net (code "29") (name "Net-(CN2G-KL)") (class "Default")
      (node (ref "CN2") (pin "5") (pinfunction "KL_5") (pintype "passive"))
      (node (ref "LD8") (pin "K") (pinfunction "C_K") (pintype "passive"))
      (node (ref "T3") (pin "C") (pinfunction "C_C") (pintype "passive"))
    )
    (net (code "30") (name "Net-(CN2H-KL)") (class "Default")
      (node (ref "CN2") (pin "6") (pinfunction "KL_6") (pintype "passive"))
      (node (ref "LD9") (pin "K") (pinfunction "C_K") (pintype "passive"))
      (node (ref "T4") (pin "C") (pinfunction "C_C") (pintype "passive"))
    )
    (net (code "31") (name "Net-(CN2I-KL)") (class "Default")
      (node (ref "CN2") (pin "7") (pinfunction "KL_7") (pintype "passive"))
      (node (ref "LD10") (pin "K") (pinfunction "C_K") (pintype "passive"))
      (node (ref "T5") (pin "C") (pinfunction "C_C") (pintype "passive"))
    )
    (net (code "32") (name "Net-(CN2J-KL)") (class "Default")
      (node (ref "CN2") (pin "8") (pinfunction "KL_8") (pintype "passive"))
      (node (ref "LD11") (pin "K") (pinfunction "C_K") (pintype "passive"))
      (node (ref "T6") (pin "C") (pinfunction "C_C") (pintype "passive"))
    )
    (net (code "33") (name "Net-(CN2K-KL)") (class "Default")
      (node (ref "CN2") (pin "9") (pinfunction "KL_9") (pintype "passive"))
      (node (ref "LD12") (pin "K") (pinfunction "C_K") (pintype "passive"))
      (node (ref "T7") (pin "C") (pinfunction "C_C") (pintype "passive"))
    )
    (net (code "34") (name "Net-(CN3A-KL)") (class "Default")
      (node (ref "CN3") (pin "1") (pinfunction "KL_1") (pintype "passive"))
      (node (ref "IC4") (pin "7") (pinfunction "OUT_7") (pintype "output"))
      (node (ref "R46") (pin "1") (pinfunction "1_1") (pintype "passive"))
    )
    (net (code "35") (name "Net-(CN4A-KL)") (class "Default")
      (node (ref "CN4") (pin "1") (pinfunction "KL_1") (pintype "passive"))
      (node (ref "R89") (pin "2") (pinfunction "2_2") (pintype "passive"))
    )
    (net (code "36") (name "Net-(CN4B-KL)") (class "Default")
      (node (ref "CN4") (pin "10") (pinfunction "KL_10") (pintype "passive"))
      (node (ref "R43") (pin "2") (pinfunction "2_2") (pintype "passive"))
    )
    (net (code "37") (name "Net-(CN4D-KL)") (class "Default")
      (node (ref "CN4") (pin "2") (pinfunction "KL_2") (pintype "passive"))
      (node (ref "R91") (pin "2") (pinfunction "2_2") (pintype "passive"))
    )
    (net (code "38") (name "Net-(CN4E-KL)") (class "Default")
      (node (ref "CN4") (pin "3") (pinfunction "KL_3") (pintype "passive"))
      (node (ref "R13") (pin "2") (pinfunction "2_2") (pintype "passive"))
    )
    (net (code "39") (name "Net-(CN4F-KL)") (class "Default")
      (node (ref "CN4") (pin "4") (pinfunction "KL_4") (pintype "passive"))
      (node (ref "R15") (pin "2") (pinfunction "2_2") (pintype "passive"))
    )
    (net (code "40") (name "Net-(CN4G-KL)") (class "Default")
      (node (ref "CN4") (pin "5") (pinfunction "KL_5") (pintype "passive"))
      (node (ref "R17") (pin "2") (pinfunction "2_2") (pintype "passive"))
    )
    (net (code "41") (name "Net-(CN4H-KL)") (class "Default")
      (node (ref "CN4") (pin "6") (pinfunction "KL_6") (pintype "passive"))
      (node (ref "R19") (pin "2") (pinfunction "2_2") (pintype "passive"))
    )
    (net (code "42") (name "Net-(CN4I-KL)") (class "Default")
      (node (ref "CN4") (pin "7") (pinfunction "KL_7") (pintype "passive"))
      (node (ref "R21") (pin "2") (pinfunction "2_2") (pintype "passive"))
    )
    (net (code "43") (name "Net-(CN4J-KL)") (class "Default")
      (node (ref "CN4") (pin "8") (pinfunction "KL_8") (pintype "passive"))
      (node (ref "R31") (pin "2") (pinfunction "2_2") (pintype "passive"))
    )
    (net (code "44") (name "Net-(CN4K-KL)") (class "Default")
      (node (ref "CN4") (pin "9") (pinfunction "KL_9") (pintype "passive"))
      (node (ref "R33") (pin "2") (pinfunction "2_2") (pintype "passive"))
    )
    (net (code "45") (name "Net-(CN5B-KL)") (class "Default")
      (node (ref "CN5") (pin "2") (pinfunction "KL_2") (pintype "passive"))
      (node (ref "R54") (pin "1") (pinfunction "1_1") (pintype "passive"))
    )
    (net (code "46") (name "Net-(CN5C-KL)") (class "Default")
      (node (ref "CN5") (pin "3") (pinfunction "KL_3") (pintype "passive"))
      (node (ref "R52") (pin "1") (pinfunction "1_1") (pintype "passive"))
    )
    (net (code "47") (name "Net-(CN5D-KL)") (class "Default")
      (node (ref "CN5") (pin "4") (pinfunction "KL_4") (pintype "passive"))
      (node (ref "R50") (pin "1") (pinfunction "1_1") (pintype "passive"))
    )
    (net (code "48") (name "Net-(CN5E-KL)") (class "Default")
      (node (ref "CN5") (pin "5") (pinfunction "KL_5") (pintype "passive"))
      (node (ref "R48") (pin "1") (pinfunction "1_1") (pintype "passive"))
    )
    (net (code "49") (name "Net-(CN10-Pad1)") (class "Default")
      (node (ref "CN10") (pin "1") (pinfunction "1_1") (pintype "passive"))
      (node (ref "D10") (pin "A") (pinfunction "A_A") (pintype "passive"))
    )
    (net (code "50") (name "Net-(CN12A-KL)") (class "Default")
      (node (ref "CN12") (pin "1") (pinfunction "KL_1") (pintype "passive"))
      (node (ref "IC11") (pin "2") (pinfunction "A1_2") (pintype "input"))
      (node (ref "RN2") (pin "2") (pinfunction "2_2") (pintype "passive"))
    )
    (net (code "51") (name "Net-(CN12B-KL)") (class "Default")
      (node (ref "CN12") (pin "2") (pinfunction "KL_2") (pintype "passive"))
      (node (ref "IC11") (pin "3") (pinfunction "A2_3") (pintype "input"))
      (node (ref "RN2") (pin "3") (pinfunction "3_3") (pintype "passive"))
    )
    (net (code "52") (name "Net-(CN12C-KL)") (class "Default")
      (node (ref "CN12") (pin "3") (pinfunction "KL_3") (pintype "passive"))
      (node (ref "IC11") (pin "4") (pinfunction "A3_4") (pintype "input"))
      (node (ref "RN2") (pin "4") (pinfunction "4_4") (pintype "passive"))
    )
    (net (code "53") (name "Net-(CN12D-KL)") (class "Default")
      (node (ref "CN12") (pin "4") (pinfunction "KL_4") (pintype "passive"))
      (node (ref "IC11") (pin "5") (pinfunction "A4_5") (pintype "input"))
      (node (ref "RN2") (pin "5") (pinfunction "5_5") (pintype "passive"))
    )
    (net (code "54") (name "Net-(CN12E-KL)") (class "Default")
      (node (ref "CN12") (pin "5") (pinfunction "KL_5") (pintype "passive"))
      (node (ref "IC11") (pin "6") (pinfunction "A5_6") (pintype "input"))
      (node (ref "RN2") (pin "6") (pinfunction "6_6") (pintype "passive"))
    )
    (net (code "55") (name "Net-(CN12F-KL)") (class "Default")
      (node (ref "CN12") (pin "6") (pinfunction "KL_6") (pintype "passive"))
      (node (ref "IC11") (pin "7") (pinfunction "A6_7") (pintype "input"))
      (node (ref "RN2") (pin "7") (pinfunction "7_7") (pintype "passive"))
    )
    (net (code "56") (name "Net-(CN12G-KL)") (class "Default")
      (node (ref "CN12") (pin "7") (pinfunction "KL_7") (pintype "passive"))
      (node (ref "IC11") (pin "8") (pinfunction "A7_8") (pintype "input"))
      (node (ref "RN2") (pin "8") (pinfunction "8_8") (pintype "passive"))
    )
    (net (code "57") (name "Net-(CN12H-KL)") (class "Default")
      (node (ref "CN12") (pin "8") (pinfunction "KL_8") (pintype "passive"))
      (node (ref "IC11") (pin "9") (pinfunction "A8_9") (pintype "input"))
      (node (ref "RN2") (pin "9") (pinfunction "9_9") (pintype "passive"))
    )
    (net (code "58") (name "Net-(CN13A-KL)") (class "Default")
      (node (ref "CN13") (pin "1") (pinfunction "KL_1") (pintype "passive"))
      (node (ref "IC12") (pin "2") (pinfunction "A1_2") (pintype "input"))
      (node (ref "RN1") (pin "2") (pinfunction "2_2") (pintype "passive"))
    )
    (net (code "59") (name "Net-(CN13B-KL)") (class "Default")
      (node (ref "CN13") (pin "2") (pinfunction "KL_2") (pintype "passive"))
      (node (ref "IC12") (pin "3") (pinfunction "A2_3") (pintype "input"))
      (node (ref "RN1") (pin "3") (pinfunction "3_3") (pintype "passive"))
    )
    (net (code "60") (name "Net-(CN13C-KL)") (class "Default")
      (node (ref "CN13") (pin "3") (pinfunction "KL_3") (pintype "passive"))
      (node (ref "IC12") (pin "4") (pinfunction "A3_4") (pintype "input"))
      (node (ref "RN1") (pin "4") (pinfunction "4_4") (pintype "passive"))
    )
    (net (code "61") (name "Net-(CN13D-KL)") (class "Default")
      (node (ref "CN13") (pin "4") (pinfunction "KL_4") (pintype "passive"))
      (node (ref "IC12") (pin "5") (pinfunction "A4_5") (pintype "input"))
      (node (ref "RN1") (pin "5") (pinfunction "5_5") (pintype "passive"))
    )
    (net (code "62") (name "Net-(CN13E-KL)") (class "Default")
      (node (ref "CN13") (pin "5") (pinfunction "KL_5") (pintype "passive"))
      (node (ref "IC12") (pin "6") (pinfunction "A5_6") (pintype "input"))
      (node (ref "RN1") (pin "6") (pinfunction "6_6") (pintype "passive"))
    )
    (net (code "63") (name "Net-(CN13F-KL)") (class "Default")
      (node (ref "CN13") (pin "6") (pinfunction "KL_6") (pintype "passive"))
      (node (ref "IC12") (pin "7") (pinfunction "A6_7") (pintype "input"))
      (node (ref "RN1") (pin "7") (pinfunction "7_7") (pintype "passive"))
    )
    (net (code "64") (name "Net-(CN13G-KL)") (class "Default")
      (node (ref "CN13") (pin "7") (pinfunction "KL_7") (pintype "passive"))
      (node (ref "IC12") (pin "8") (pinfunction "A7_8") (pintype "input"))
      (node (ref "RN1") (pin "8") (pinfunction "8_8") (pintype "passive"))
    )
    (net (code "65") (name "Net-(CN13H-KL)") (class "Default")
      (node (ref "CN13") (pin "8") (pinfunction "KL_8") (pintype "passive"))
      (node (ref "IC12") (pin "9") (pinfunction "A8_9") (pintype "input"))
      (node (ref "RN1") (pin "9") (pinfunction "9_9") (pintype "passive"))
    )
    (net (code "66") (name "Net-(CN14A-KL)") (class "Default")
      (node (ref "CN14") (pin "1") (pinfunction "KL_1") (pintype "passive"))
      (node (ref "K2") (pin "6") (pinfunction "P_6") (pintype "passive"))
    )
    (net (code "67") (name "Net-(CN14B-KL)") (class "Default")
      (node (ref "CN14") (pin "2") (pinfunction "KL_2") (pintype "passive"))
      (node (ref "CN14") (pin "4") (pinfunction "KL_4") (pintype "passive"))
      (node (ref "CN14") (pin "6") (pinfunction "KL_6") (pintype "passive"))
      (node (ref "CN14") (pin "8") (pinfunction "KL_8") (pintype "passive"))
      (node (ref "CN15") (pin "2") (pinfunction "KL_2") (pintype "passive"))
      (node (ref "CN15") (pin "4") (pinfunction "KL_4") (pintype "passive"))
      (node (ref "CN15") (pin "6") (pinfunction "KL_6") (pintype "passive"))
      (node (ref "CN15") (pin "8") (pinfunction "KL_8") (pintype "passive"))
      (node (ref "K1") (pin "P1") (pinfunction "P_P1") (pintype "passive"))
    )
    (net (code "68") (name "Net-(CN14C-KL)") (class "Default")
      (node (ref "CN14") (pin "3") (pinfunction "KL_3") (pintype "passive"))
      (node (ref "K3") (pin "6") (pinfunction "P_6") (pintype "passive"))
    )
    (net (code "69") (name "Net-(CN14E-KL)") (class "Default")
      (node (ref "CN14") (pin "5") (pinfunction "KL_5") (pintype "passive"))
      (node (ref "K4") (pin "6") (pinfunction "P_6") (pintype "passive"))
    )
    (net (code "70") (name "Net-(CN14G-KL)") (class "Default")
      (node (ref "CN14") (pin "7") (pinfunction "KL_7") (pintype "passive"))
      (node (ref "K5") (pin "6") (pinfunction "P_6") (pintype "passive"))
    )
    (net (code "71") (name "Net-(CN15A-KL)") (class "Default")
      (node (ref "CN15") (pin "1") (pinfunction "KL_1") (pintype "passive"))
      (node (ref "K6") (pin "6") (pinfunction "P_6") (pintype "passive"))
    )
    (net (code "72") (name "Net-(CN15C-KL)") (class "Default")
      (node (ref "CN15") (pin "3") (pinfunction "KL_3") (pintype "passive"))
      (node (ref "K7") (pin "6") (pinfunction "P_6") (pintype "passive"))
    )
    (net (code "73") (name "Net-(CN15E-KL)") (class "Default")
      (node (ref "CN15") (pin "5") (pinfunction "KL_5") (pintype "passive"))
      (node (ref "K8") (pin "6") (pinfunction "P_6") (pintype "passive"))
    )
    (net (code "74") (name "Net-(CN15G-KL)") (class "Default")
      (node (ref "CN15") (pin "7") (pinfunction "KL_7") (pintype "passive"))
      (node (ref "K9") (pin "6") (pinfunction "P_6") (pintype "passive"))
    )
    (net (code "75") (name "Net-(IC1-OSC1{slash}CLKI)") (class "Default")
      (node (ref "C1") (pin "2") (pinfunction "2_2") (pintype "passive"))
      (node (ref "IC1") (pin "13") (pinfunction "OSC1/CLKI_13") (pintype "input"))
      (node (ref "X1") (pin "2") (pinfunction "2_2") (pintype "passive"))
    )
    (net (code "76") (name "Net-(IC1-RA0{slash}AN0)") (class "Default")
      (node (ref "IC1") (pin "2") (pinfunction "RA0/AN0_2") (pintype "bidirectional"))
      (node (ref "IC5") (pin "1") (pinfunction "OUT_1") (pintype "output"))
      (node (ref "R2") (pin "1") (pinfunction "1_1") (pintype "passive"))
    )
    (net (code "77") (name "Net-(IC1-RA1{slash}AN1)") (class "Default")
      (node (ref "IC1") (pin "3") (pinfunction "RA1/AN1_3") (pintype "bidirectional"))
      (node (ref "IC5") (pin "7") (pinfunction "OUT_7") (pintype "output"))
      (node (ref "R4") (pin "1") (pinfunction "1_1") (pintype "passive"))
    )
    (net (code "78") (name "Net-(IC1-RA2{slash}AN2{slash}VREF-{slash}CVREF)") (class "Default")
      (node (ref "IC1") (pin "4") (pinfunction "RA2/AN2/VREF-/CVREF_4") (pintype "bidirectional"))
      (node (ref "IC2") (pin "1") (pinfunction "OUT_1") (pintype "output"))
      (node (ref "R6") (pin "1") (pinfunction "1_1") (pintype "passive"))
    )
    (net (code "79") (name "Net-(IC1-RA3{slash}AN3{slash}VREF+)") (class "Default")
      (node (ref "C7") (pin "+") (pinfunction "+_+") (pintype "passive"))
      (node (ref "C8") (pin "2") (pinfunction "2_2") (pintype "passive"))
      (node (ref "IC1") (pin "5") (pinfunction "RA3/AN3/VREF+_5") (pintype "bidirectional"))
      (node (ref "R10") (pin "1") (pinfunction "1_1") (pintype "passive"))
      (node (ref "R11") (pin "1") (pinfunction "1_1") (pintype "passive"))
      (node (ref "VR1") (pin "C") (pinfunction "C_C") (pintype "passive"))
    )
    (net (code "80") (name "Net-(IC1-RA5{slash}AN4{slash}~{SS}{slash}HLVDIN{slash}C2OUT)") (class "Default")
      (node (ref "IC1") (pin "7") (pinfunction "RA5/AN4/~{SS}/HLVDIN/C2OUT_7") (pintype "bidirectional"))
      (node (ref "IC2") (pin "7") (pinfunction "OUT_7") (pintype "output"))
      (node (ref "R8") (pin "1") (pinfunction "1_1") (pintype "passive"))
    )
    (net (code "81") (name "Net-(IC1-RA6{slash}OSC2{slash}CLKO)") (class "Default")
      (node (ref "C2") (pin "2") (pinfunction "2_2") (pintype "passive"))
      (node (ref "IC1") (pin "14") (pinfunction "RA6/OSC2/CLKO_14") (pintype "output"))
      (node (ref "X1") (pin "1") (pinfunction "1_1") (pintype "passive"))
    )
    (net (code "82") (name "Net-(IC1-RB0{slash}AN12{slash}INT0{slash}LFT0{slash}SDI{slash}SDA)") (class "Default")
      (node (ref "CN7") (pin "3") (pinfunction "3_3") (pintype "passive"))
      (node (ref "IC1") (pin "33") (pinfunction "RB0/AN12/INT0/LFT0/SDI/SDA_33") (pintype "bidirectional"))
    )
    (net (code "83") (name "Net-(IC1-RB1{slash}AN10{slash}INT1{slash}SCK{slash}SCL)") (class "Default")
      (node (ref "CN7") (pin "2") (pinfunction "2_2") (pintype "passive"))
      (node (ref "IC1") (pin "34") (pinfunction "RB1/AN10/INT1/SCK/SCL_34") (pintype "bidirectional"))
    )
    (net (code "84") (name "Net-(IC1-RB3{slash}AN9{slash}CCP2{slash}VPO)") (class "Default")
      (node (ref "IC1") (pin "36") (pinfunction "RB3/AN9/CCP2/VPO_36") (pintype "bidirectional"))
      (node (ref "R45") (pin "2") (pinfunction "2_2") (pintype "passive"))
    )
    (net (code "85") (name "Net-(IC1-RB6{slash}KBI2{slash}PGC)") (class "Default")
      (node (ref "CN8") (pin "5") (pinfunction "5_5") (pintype "passive"))
      (node (ref "IC1") (pin "39") (pinfunction "RB6/KBI2/PGC_39") (pintype "bidirectional"))
    )
    (net (code "86") (name "Net-(IC1-RB7{slash}BKI3{slash}PGD)") (class "Default")
      (node (ref "CN8") (pin "4") (pinfunction "4_4") (pintype "passive"))
      (node (ref "IC1") (pin "40") (pinfunction "RB7/BKI3/PGD_40") (pintype "bidirectional"))
    )
    (net (code "87") (name "Net-(IC1-RC0{slash}TIOSO{slash}T13CKI)") (class "Default")
      (node (ref "C3") (pin "2") (pinfunction "2_2") (pintype "passive"))
      (node (ref "IC1") (pin "15") (pinfunction "RC0/TIOSO/T13CKI_15") (pintype "bidirectional"))
      (node (ref "X2") (pin "2") (pinfunction "2_2") (pintype "passive"))
    )
    (net (code "88") (name "Net-(IC1-RC1{slash}T1OSI{slash}ICCP2{slash}~{UOE})") (class "Default")
      (node (ref "C4") (pin "2") (pinfunction "2_2") (pintype "passive"))
      (node (ref "IC1") (pin "16") (pinfunction "RC1/T1OSI/ICCP2/~{UOE}_16") (pintype "bidirectional"))
      (node (ref "X2") (pin "1") (pinfunction "1_1") (pintype "passive"))
    )
    (net (code "89") (name "Net-(IC1-RC4{slash}D-{slash}VM)") (class "Default")
      (node (ref "CN9") (pin "3") (pinfunction "3_3") (pintype "passive"))
      (node (ref "IC1") (pin "23") (pinfunction "RC4/D-/VM_23") (pintype "bidirectional"))
    )
    (net (code "90") (name "Net-(IC1-RC5{slash}D+{slash}VP)") (class "Default")
      (node (ref "CN9") (pin "2") (pinfunction "2_2") (pintype "passive"))
      (node (ref "IC1") (pin "24") (pinfunction "RC5/D+/VP_24") (pintype "bidirectional"))
    )
    (net (code "91") (name "Net-(IC1-VUSB)") (class "Default")
      (node (ref "C17") (pin "2") (pinfunction "2_2") (pintype "passive"))
      (node (ref "IC1") (pin "18") (pinfunction "VUSB_18") (pintype "bidirectional"))
    )
    (net (code "92") (name "Net-(IC1-~{MCLR}{slash}VPP{slash}RE3)") (class "Default")
      (node (ref "CN11") (pin "1") (pinfunction "1_1") (pintype "passive"))
      (node (ref "CN8") (pin "1") (pinfunction "1_1") (pintype "passive"))
      (node (ref "IC1") (pin "1") (pinfunction "~{MCLR}/VPP/RE3_1") (pintype "input"))
      (node (ref "R1") (pin "1") (pinfunction "1_1") (pintype "passive"))
    )
    (net (code "93") (name "Net-(IC2A-+IN)") (class "Default")
      (node (ref "C14") (pin "2") (pinfunction "2_2") (pintype "passive"))
      (node (ref "IC2") (pin "3") (pinfunction "+IN_3") (pintype "input"))
      (node (ref "R50") (pin "2") (pinfunction "2_2") (pintype "passive"))
      (node (ref "R51") (pin "2") (pinfunction "2_2") (pintype "passive"))
    )
    (net (code "94") (name "Net-(IC2A--IN)") (class "Default")
      (node (ref "IC2") (pin "2") (pinfunction "-IN_2") (pintype "input"))
      (node (ref "R6") (pin "2") (pinfunction "2_2") (pintype "passive"))
      (node (ref "R7") (pin "1") (pinfunction "1_1") (pintype "passive"))
    )
    (net (code "95") (name "Net-(IC2B-+IN)") (class "Default")
      (node (ref "C13") (pin "2") (pinfunction "2_2") (pintype "passive"))
      (node (ref "IC2") (pin "5") (pinfunction "+IN_5") (pintype "input"))
      (node (ref "R48") (pin "2") (pinfunction "2_2") (pintype "passive"))
      (node (ref "R49") (pin "2") (pinfunction "2_2") (pintype "passive"))
    )
    (net (code "96") (name "Net-(IC2B--IN)") (class "Default")
      (node (ref "IC2") (pin "6") (pinfunction "-IN_6") (pintype "input"))
      (node (ref "R8") (pin "2") (pinfunction "2_2") (pintype "passive"))
      (node (ref "R9") (pin "1") (pinfunction "1_1") (pintype "passive"))
    )
    (net (code "97") (name "Net-(IC3A-A1)") (class "Default")
      (node (ref "IC3") (pin "2") (pinfunction "A1_2") (pintype "input"))
      (node (ref "LD1") (pin "K") (pinfunction "C_K") (pintype "passive"))
      (node (ref "R14") (pin "2") (pinfunction "2_2") (pintype "passive"))
    )
    (net (code "98") (name "Net-(IC3A-A2)") (class "Default")
      (node (ref "IC3") (pin "3") (pinfunction "A2_3") (pintype "input"))
      (node (ref "LD2") (pin "K") (pinfunction "C_K") (pintype "passive"))
      (node (ref "R16") (pin "2") (pinfunction "2_2") (pintype "passive"))
    )
    (net (code "99") (name "Net-(IC3A-A3)") (class "Default")
      (node (ref "IC3") (pin "4") (pinfunction "A3_4") (pintype "input"))
      (node (ref "LD3") (pin "K") (pinfunction "C_K") (pintype "passive"))
      (node (ref "R18") (pin "2") (pinfunction "2_2") (pintype "passive"))
    )
    (net (code "100") (name "Net-(IC3A-A4)") (class "Default")
      (node (ref "IC3") (pin "5") (pinfunction "A4_5") (pintype "input"))
      (node (ref "LD4") (pin "K") (pinfunction "C_K") (pintype "passive"))
      (node (ref "R20") (pin "2") (pinfunction "2_2") (pintype "passive"))
    )
    (net (code "101") (name "Net-(IC3A-A5)") (class "Default")
      (node (ref "IC3") (pin "6") (pinfunction "A5_6") (pintype "input"))
      (node (ref "LD5") (pin "K") (pinfunction "C_K") (pintype "passive"))
      (node (ref "R22") (pin "2") (pinfunction "2_2") (pintype "passive"))
    )
    (net (code "102") (name "Net-(IC3A-A6)") (class "Default")
      (node (ref "IC3") (pin "7") (pinfunction "A6_7") (pintype "input"))
      (node (ref "LD14") (pin "K") (pinfunction "C_K") (pintype "passive"))
      (node (ref "R32") (pin "2") (pinfunction "2_2") (pintype "passive"))
    )
    (net (code "103") (name "Net-(IC3A-A7)") (class "Default")
      (node (ref "IC3") (pin "8") (pinfunction "A7_8") (pintype "input"))
      (node (ref "LD15") (pin "K") (pinfunction "C_K") (pintype "passive"))
      (node (ref "R42") (pin "2") (pinfunction "2_2") (pintype "passive"))
    )
    (net (code "104") (name "Net-(IC3A-A8)") (class "Default")
      (node (ref "IC3") (pin "9") (pinfunction "A8_9") (pintype "input"))
      (node (ref "LD16") (pin "K") (pinfunction "C_K") (pintype "passive"))
      (node (ref "R44") (pin "2") (pinfunction "2_2") (pintype "passive"))
    )
    (net (code "105") (name "Net-(IC4A-+IN)") (class "Default")
      (node (ref "C11") (pin "2") (pinfunction "2_2") (pintype "passive"))
      (node (ref "IC4") (pin "3") (pinfunction "+IN_3") (pintype "input"))
      (node (ref "R45") (pin "1") (pinfunction "1_1") (pintype "passive"))
    )
    (net (code "106") (name "Net-(IC4A--IN)") (class "Default")
      (node (ref "IC4") (pin "1") (pinfunction "OUT_1") (pintype "output"))
      (node (ref "IC4") (pin "2") (pinfunction "-IN_2") (pintype "input"))
      (node (ref "IC4") (pin "5") (pinfunction "+IN_5") (pintype "input"))
    )
    (net (code "107") (name "Net-(IC4B--IN)") (class "Default")
      (node (ref "IC4") (pin "6") (pinfunction "-IN_6") (pintype "input"))
      (node (ref "R46") (pin "2") (pinfunction "2_2") (pintype "passive"))
      (node (ref "R47") (pin "1") (pinfunction "1_1") (pintype "passive"))
    )
    (net (code "108") (name "Net-(IC5A-+IN)") (class "Default")
      (node (ref "C16") (pin "2") (pinfunction "2_2") (pintype "passive"))
      (node (ref "IC5") (pin "3") (pinfunction "+IN_3") (pintype "input"))
      (node (ref "R54") (pin "2") (pinfunction "2_2") (pintype "passive"))
      (node (ref "R55") (pin "2") (pinfunction "2_2") (pintype "passive"))
    )
    (net (code "109") (name "Net-(IC5A--IN)") (class "Default")
      (node (ref "IC5") (pin "2") (pinfunction "-IN_2") (pintype "input"))
      (node (ref "R2") (pin "2") (pinfunction "2_2") (pintype "passive"))
      (node (ref "R3") (pin "1") (pinfunction "1_1") (pintype "passive"))
    )
    (net (code "110") (name "Net-(IC5B-+IN)") (class "Default")
      (node (ref "C15") (pin "2") (pinfunction "2_2") (pintype "passive"))
      (node (ref "IC5") (pin "5") (pinfunction "+IN_5") (pintype "input"))
      (node (ref "R52") (pin "2") (pinfunction "2_2") (pintype "passive"))
      (node (ref "R53") (pin "2") (pinfunction "2_2") (pintype "passive"))
    )
    (net (code "111") (name "Net-(IC5B--IN)") (class "Default")
      (node (ref "IC5") (pin "6") (pinfunction "-IN_6") (pintype "input"))
      (node (ref "R4") (pin "2") (pinfunction "2_2") (pintype "passive"))
      (node (ref "R5") (pin "1") (pinfunction "1_1") (pintype "passive"))
    )
    (net (code "112") (name "Net-(IC6-OUT)") (class "Default")
      (node (ref "D9") (pin "C") (pinfunction "C_C") (pintype "passive"))
      (node (ref "IC6") (pin "2") (pinfunction "OUT_2") (pintype "output"))
      (node (ref "L1") (pin "1") (pinfunction "1_1") (pintype "passive"))
    )
    (net (code "113") (name "Net-(IC8A-1Q)") (class "Default")
      (node (ref "IC8") (pin "19") (pinfunction "1Q_19") (pintype "tri_state"))
      (node (ref "R23") (pin "1") (pinfunction "1_1") (pintype "passive"))
    )
    (net (code "114") (name "Net-(IC8A-2Q)") (class "Default")
      (node (ref "IC8") (pin "18") (pinfunction "2Q_18") (pintype "tri_state"))
      (node (ref "R24") (pin "1") (pinfunction "1_1") (pintype "passive"))
    )
    (net (code "115") (name "Net-(IC8A-3Q)") (class "Default")
      (node (ref "IC8") (pin "17") (pinfunction "3Q_17") (pintype "tri_state"))
      (node (ref "R25") (pin "1") (pinfunction "1_1") (pintype "passive"))
    )
    (net (code "116") (name "Net-(IC8A-4Q)") (class "Default")
      (node (ref "IC8") (pin "16") (pinfunction "4Q_16") (pintype "tri_state"))
      (node (ref "R26") (pin "1") (pinfunction "1_1") (pintype "passive"))
    )
    (net (code "117") (name "Net-(IC8A-5Q)") (class "Default")
      (node (ref "IC8") (pin "15") (pinfunction "5Q_15") (pintype "tri_state"))
      (node (ref "R27") (pin "1") (pinfunction "1_1") (pintype "passive"))
    )
    (net (code "118") (name "Net-(IC8A-6Q)") (class "Default")
      (node (ref "IC8") (pin "14") (pinfunction "6Q_14") (pintype "tri_state"))
      (node (ref "R28") (pin "1") (pinfunction "1_1") (pintype "passive"))
    )
    (net (code "119") (name "Net-(IC8A-7Q)") (class "Default")
      (node (ref "IC8") (pin "13") (pinfunction "7Q_13") (pintype "tri_state"))
      (node (ref "R29") (pin "1") (pinfunction "1_1") (pintype "passive"))
    )
    (net (code "120") (name "Net-(IC8A-8Q)") (class "Default")
      (node (ref "IC8") (pin "12") (pinfunction "8Q_12") (pintype "tri_state"))
      (node (ref "R30") (pin "1") (pinfunction "1_1") (pintype "passive"))
    )
    (net (code "121") (name "Net-(IC13-I1)") (class "Default")
      (node (ref "IC13") (pin "1") (pinfunction "I1_1") (pintype "input"))
      (node (ref "IC14") (pin "19") (pinfunction "1Q_19") (pintype "tri_state"))
    )
    (net (code "122") (name "Net-(IC13-I2)") (class "Default")
      (node (ref "IC13") (pin "2") (pinfunction "I2_2") (pintype "input"))
      (node (ref "IC14") (pin "18") (pinfunction "2Q_18") (pintype "tri_state"))
    )
    (net (code "123") (name "Net-(IC13-I3)") (class "Default")
      (node (ref "IC13") (pin "3") (pinfunction "I3_3") (pintype "input"))
      (node (ref "IC14") (pin "17") (pinfunction "3Q_17") (pintype "tri_state"))
    )
    (net (code "124") (name "Net-(IC13-I4)") (class "Default")
      (node (ref "IC13") (pin "4") (pinfunction "I4_4") (pintype "input"))
      (node (ref "IC14") (pin "16") (pinfunction "4Q_16") (pintype "tri_state"))
    )
    (net (code "125") (name "Net-(IC13-I5)") (class "Default")
      (node (ref "IC13") (pin "5") (pinfunction "I5_5") (pintype "input"))
      (node (ref "IC14") (pin "15") (pinfunction "5Q_15") (pintype "tri_state"))
    )
    (net (code "126") (name "Net-(IC13-I6)") (class "Default")
      (node (ref "IC13") (pin "6") (pinfunction "I6_6") (pintype "input"))
      (node (ref "IC14") (pin "14") (pinfunction "6Q_14") (pintype "tri_state"))
    )
    (net (code "127") (name "Net-(IC13-I7)") (class "Default")
      (node (ref "IC13") (pin "7") (pinfunction "I7_7") (pintype "input"))
      (node (ref "IC14") (pin "13") (pinfunction "7Q_13") (pintype "tri_state"))
    )
    (net (code "128") (name "Net-(IC13-I8)") (class "Default")
      (node (ref "IC13") (pin "8") (pinfunction "I8_8") (pintype "input"))
      (node (ref "IC14") (pin "12") (pinfunction "8Q_12") (pintype "tri_state"))
    )
    (net (code "129") (name "Net-(IC13-O1)") (class "Default")
      (node (ref "IC13") (pin "18") (pinfunction "O1_18") (pintype "open_collector"))
      (node (ref "K2") (pin "8") (pinfunction "2_8") (pintype "passive"))
    )
    (net (code "130") (name "Net-(IC13-O2)") (class "Default")
      (node (ref "IC13") (pin "17") (pinfunction "O2_17") (pintype "open_collector"))
      (node (ref "K3") (pin "8") (pinfunction "2_8") (pintype "passive"))
    )
    (net (code "131") (name "Net-(IC13-O3)") (class "Default")
      (node (ref "IC13") (pin "16") (pinfunction "O3_16") (pintype "open_collector"))
      (node (ref "K4") (pin "8") (pinfunction "2_8") (pintype "passive"))
    )
    (net (code "132") (name "Net-(IC13-O4)") (class "Default")
      (node (ref "IC13") (pin "15") (pinfunction "O4_15") (pintype "open_collector"))
      (node (ref "K5") (pin "8") (pinfunction "2_8") (pintype "passive"))
    )
    (net (code "133") (name "Net-(IC13-O5)") (class "Default")
      (node (ref "IC13") (pin "14") (pinfunction "O5_14") (pintype "open_collector"))
      (node (ref "K6") (pin "8") (pinfunction "2_8") (pintype "passive"))
    )
    (net (code "134") (name "Net-(IC13-O6)") (class "Default")
      (node (ref "IC13") (pin "13") (pinfunction "O6_13") (pintype "open_collector"))
      (node (ref "K7") (pin "8") (pinfunction "2_8") (pintype "passive"))
    )
    (net (code "135") (name "Net-(IC13-O7)") (class "Default")
      (node (ref "IC13") (pin "12") (pinfunction "O7_12") (pintype "open_collector"))
      (node (ref "K8") (pin "8") (pinfunction "2_8") (pintype "passive"))
    )
    (net (code "136") (name "Net-(IC13-O8)") (class "Default")
      (node (ref "IC13") (pin "11") (pinfunction "O8_11") (pintype "open_collector"))
      (node (ref "K9") (pin "8") (pinfunction "2_8") (pintype "passive"))
    )
    (net (code "137") (name "Net-(IC15-OUT)") (class "Default")
      (node (ref "D1") (pin "C") (pinfunction "C_C") (pintype "passive"))
      (node (ref "IC15") (pin "2") (pinfunction "OUT_2") (pintype "output"))
      (node (ref "L2") (pin "1") (pinfunction "1_1") (pintype "passive"))
    )
    (net (code "138") (name "Net-(K1A-2)") (class "Default")
      (node (ref "D3") (pin "A") (pinfunction "A_A") (pintype "passive"))
      (node (ref "K1") (pin "16") (pinfunction "2_16") (pintype "passive"))
      (node (ref "T11") (pin "3") (pinfunction "C_3") (pintype "passive"))
    )
    (net (code "139") (name "Net-(K1C-P)") (class "Default")
      (node (ref "K1") (pin "P2") (pinfunction "P_P2") (pintype "passive"))
      (node (ref "K2") (pin "4") (pinfunction "S_4") (pintype "passive"))
      (node (ref "K3") (pin "4") (pinfunction "S_4") (pintype "passive"))
      (node (ref "K4") (pin "4") (pinfunction "S_4") (pintype "passive"))
      (node (ref "K5") (pin "4") (pinfunction "S_4") (pintype "passive"))
      (node (ref "K6") (pin "4") (pinfunction "S_4") (pintype "passive"))
      (node (ref "K7") (pin "4") (pinfunction "S_4") (pintype "passive"))
      (node (ref "K8") (pin "4") (pinfunction "S_4") (pintype "passive"))
      (node (ref "K9") (pin "4") (pinfunction "S_4") (pintype "passive"))
    )
    (net (code "140") (name "Net-(LD1-PadA)") (class "Default")
      (node (ref "LD1") (pin "A") (pinfunction "A_A") (pintype "passive"))
      (node (ref "R13") (pin "1") (pinfunction "1_1") (pintype "passive"))
    )
    (net (code "141") (name "Net-(LD2-PadA)") (class "Default")
      (node (ref "LD2") (pin "A") (pinfunction "A_A") (pintype "passive"))
      (node (ref "R15") (pin "1") (pinfunction "1_1") (pintype "passive"))
    )
    (net (code "142") (name "Net-(LD3-PadA)") (class "Default")
      (node (ref "LD3") (pin "A") (pinfunction "A_A") (pintype "passive"))
      (node (ref "R17") (pin "1") (pinfunction "1_1") (pintype "passive"))
    )
    (net (code "143") (name "Net-(LD4-PadA)") (class "Default")
      (node (ref "LD4") (pin "A") (pinfunction "A_A") (pintype "passive"))
      (node (ref "R19") (pin "1") (pinfunction "1_1") (pintype "passive"))
    )
    (net (code "144") (name "Net-(LD5-PadA)") (class "Default")
      (node (ref "LD5") (pin "A") (pinfunction "A_A") (pintype "passive"))
      (node (ref "R21") (pin "1") (pinfunction "1_1") (pintype "passive"))
    )
    (net (code "145") (name "Net-(LD6-PadA)") (class "Default")
      (node (ref "LD6") (pin "A") (pinfunction "A_A") (pintype "passive"))
      (node (ref "R34") (pin "2") (pinfunction "2_2") (pintype "passive"))
    )
    (net (code "146") (name "Net-(LD7-PadA)") (class "Default")
      (node (ref "LD7") (pin "A") (pinfunction "A_A") (pintype "passive"))
      (node (ref "R35") (pin "2") (pinfunction "2_2") (pintype "passive"))
    )
    (net (code "147") (name "Net-(LD8-PadA)") (class "Default")
      (node (ref "LD8") (pin "A") (pinfunction "A_A") (pintype "passive"))
      (node (ref "R36") (pin "2") (pinfunction "2_2") (pintype "passive"))
    )
    (net (code "148") (name "Net-(LD9-PadA)") (class "Default")
      (node (ref "LD9") (pin "A") (pinfunction "A_A") (pintype "passive"))
      (node (ref "R37") (pin "2") (pinfunction "2_2") (pintype "passive"))
    )
    (net (code "149") (name "Net-(LD10-PadA)") (class "Default")
      (node (ref "LD10") (pin "A") (pinfunction "A_A") (pintype "passive"))
      (node (ref "R38") (pin "2") (pinfunction "2_2") (pintype "passive"))
    )
    (net (code "150") (name "Net-(LD11-PadA)") (class "Default")
      (node (ref "LD11") (pin "A") (pinfunction "A_A") (pintype "passive"))
      (node (ref "R39") (pin "2") (pinfunction "2_2") (pintype "passive"))
    )
    (net (code "151") (name "Net-(LD12-PadA)") (class "Default")
      (node (ref "LD12") (pin "A") (pinfunction "A_A") (pintype "passive"))
      (node (ref "R40") (pin "2") (pinfunction "2_2") (pintype "passive"))
    )
    (net (code "152") (name "Net-(LD13-PadA)") (class "Default")
      (node (ref "LD13") (pin "A") (pinfunction "A_A") (pintype "passive"))
      (node (ref "R41") (pin "2") (pinfunction "2_2") (pintype "passive"))
    )
    (net (code "153") (name "Net-(LD14-PadA)") (class "Default")
      (node (ref "LD14") (pin "A") (pinfunction "A_A") (pintype "passive"))
      (node (ref "R31") (pin "1") (pinfunction "1_1") (pintype "passive"))
    )
    (net (code "154") (name "Net-(LD15-PadA)") (class "Default")
      (node (ref "LD15") (pin "A") (pinfunction "A_A") (pintype "passive"))
      (node (ref "R33") (pin "1") (pinfunction "1_1") (pintype "passive"))
    )
    (net (code "155") (name "Net-(LD16-PadA)") (class "Default")
      (node (ref "LD16") (pin "A") (pinfunction "A_A") (pintype "passive"))
      (node (ref "R43") (pin "1") (pinfunction "1_1") (pintype "passive"))
    )
    (net (code "156") (name "Net-(LD17-PadA)") (class "Default")
      (node (ref "LD17") (pin "A") (pinfunction "A_A") (pintype "passive"))
      (node (ref "R58") (pin "2") (pinfunction "2_2") (pintype "passive"))
    )
    (net (code "157") (name "Net-(LD18-PadA)") (class "Default")
      (node (ref "LD18") (pin "A") (pinfunction "A_A") (pintype "passive"))
      (node (ref "R59") (pin "2") (pinfunction "2_2") (pintype "passive"))
    )
    (net (code "158") (name "Net-(LD19-PadA)") (class "Default")
      (node (ref "LD19") (pin "A") (pinfunction "A_A") (pintype "passive"))
      (node (ref "R89") (pin "1") (pinfunction "1_1") (pintype "passive"))
    )
    (net (code "159") (name "Net-(LD20-PadA)") (class "Default")
      (node (ref "LD20") (pin "A") (pinfunction "A_A") (pintype "passive"))
      (node (ref "R91") (pin "1") (pinfunction "1_1") (pintype "passive"))
    )
    (net (code "160") (name "Net-(R11-Pad2)") (class "Default")
      (node (ref "R11") (pin "2") (pinfunction "2_2") (pintype "passive"))
      (node (ref "R12") (pin "1") (pinfunction "1_1") (pintype "passive"))
      (node (ref "VR1") (pin "R") (pinfunction "R_R") (pintype "passive"))
    )
    (net (code "161") (name "Net-(R23-Pad2)") (class "Default")
      (node (ref "R23") (pin "2") (pinfunction "2_2") (pintype "passive"))
      (node (ref "T1") (pin "B") (pinfunction "B_B") (pintype "passive"))
    )
    (net (code "162") (name "Net-(R24-Pad2)") (class "Default")
      (node (ref "R24") (pin "2") (pinfunction "2_2") (pintype "passive"))
      (node (ref "T2") (pin "B") (pinfunction "B_B") (pintype "passive"))
    )
    (net (code "163") (name "Net-(R25-Pad2)") (class "Default")
      (node (ref "R25") (pin "2") (pinfunction "2_2") (pintype "passive"))
      (node (ref "T3") (pin "B") (pinfunction "B_B") (pintype "passive"))
    )
    (net (code "164") (name "Net-(R26-Pad2)") (class "Default")
      (node (ref "R26") (pin "2") (pinfunction "2_2") (pintype "passive"))
      (node (ref "T4") (pin "B") (pinfunction "B_B") (pintype "passive"))
    )
    (net (code "165") (name "Net-(R27-Pad2)") (class "Default")
      (node (ref "R27") (pin "2") (pinfunction "2_2") (pintype "passive"))
      (node (ref "T5") (pin "B") (pinfunction "B_B") (pintype "passive"))
    )
    (net (code "166") (name "Net-(R28-Pad2)") (class "Default")
      (node (ref "R28") (pin "2") (pinfunction "2_2") (pintype "passive"))
      (node (ref "T6") (pin "B") (pinfunction "B_B") (pintype "passive"))
    )
    (net (code "167") (name "Net-(R29-Pad2)") (class "Default")
      (node (ref "R29") (pin "2") (pinfunction "2_2") (pintype "passive"))
      (node (ref "T7") (pin "B") (pinfunction "B_B") (pintype "passive"))
    )
    (net (code "168") (name "Net-(R30-Pad2)") (class "Default")
      (node (ref "R30") (pin "2") (pinfunction "2_2") (pintype "passive"))
      (node (ref "T8") (pin "B") (pinfunction "B_B") (pintype "passive"))
    )
    (net (code "169") (name "Net-(R56-Pad2)") (class "Default")
      (node (ref "R56") (pin "2") (pinfunction "2_2") (pintype "passive"))
      (node (ref "T9") (pin "B") (pinfunction "B_B") (pintype "passive"))
    )
    (net (code "170") (name "Net-(R57-Pad2)") (class "Default")
      (node (ref "R57") (pin "2") (pinfunction "2_2") (pintype "passive"))
      (node (ref "T10") (pin "B") (pinfunction "B_B") (pintype "passive"))
    )
    (net (code "171") (name "Net-(T11-B)") (class "Default")
      (node (ref "R88") (pin "1") (pinfunction "1_1") (pintype "passive"))
      (node (ref "T11") (pin "2") (pinfunction "B_2") (pintype "passive"))
    )
    (net (code "172") (name "OUT0") (class "Default")
      (node (ref "IC1") (pin "35") (pinfunction "RB2/AN8/INT2/VMO_35") (pintype "bidirectional"))
      (node (ref "R56") (pin "1") (pinfunction "1_1") (pintype "passive"))
    )
    (net (code "173") (name "OUT1") (class "Default")
      (node (ref "IC1") (pin "37") (pinfunction "RB4/AN11/KBI0/CSSPP_37") (pintype "bidirectional"))
      (node (ref "R57") (pin "1") (pinfunction "1_1") (pintype "passive"))
    )
    (net (code "174") (name "RELE") (class "Default")
      (node (ref "IC1") (pin "38") (pinfunction "RB5/KBI1/PGM_38") (pintype "bidirectional"))
      (node (ref "R88") (pin "2") (pinfunction "2_2") (pintype "passive"))
    )
    (net (code "175") (name "RX") (class "Default")
      (node (ref "CN6") (pin "3") (pinfunction "3_3") (pintype "passive"))
      (node (ref "IC1") (pin "26") (pinfunction "RC7/RX/DT/SDO_26") (pintype "bidirectional"))
    )
    (net (code "176") (name "TX") (class "Default")
      (node (ref "CN6") (pin "2") (pinfunction "2_2") (pintype "passive"))
      (node (ref "IC1") (pin "25") (pinfunction "RC6/TX/CK_25") (pintype "bidirectional"))
    )
    (net (code "177") (name "V+") (class "Default")
      (node (ref "C9") (pin "+") (pinfunction "+_+") (pintype "passive"))
      (node (ref "D2") (pin "C") (pinfunction "C_C") (pintype "passive"))
      (node (ref "IC6") (pin "1") (pinfunction "VIN_1") (pintype "input"))
    )
    (net (code "178") (name "unconnected-(IC7A-Y0-Pad15)") (class "Default")
      (node (ref "IC7") (pin "15") (pinfunction "Y0_15") (pintype "output"))
    )
    (net (code "179") (name "unconnected-(IC7A-Y6-Pad9)") (class "Default")
      (node (ref "IC7") (pin "9") (pinfunction "Y6_9") (pintype "output"))
    )
    (net (code "180") (name "unconnected-(IC7A-Y7-Pad7)") (class "Default")
      (node (ref "IC7") (pin "7") (pinfunction "Y7_7") (pintype "output"))
    )
  )
)
